# tottag.net
KiCad netlist of a schematic drawn in EAGLE
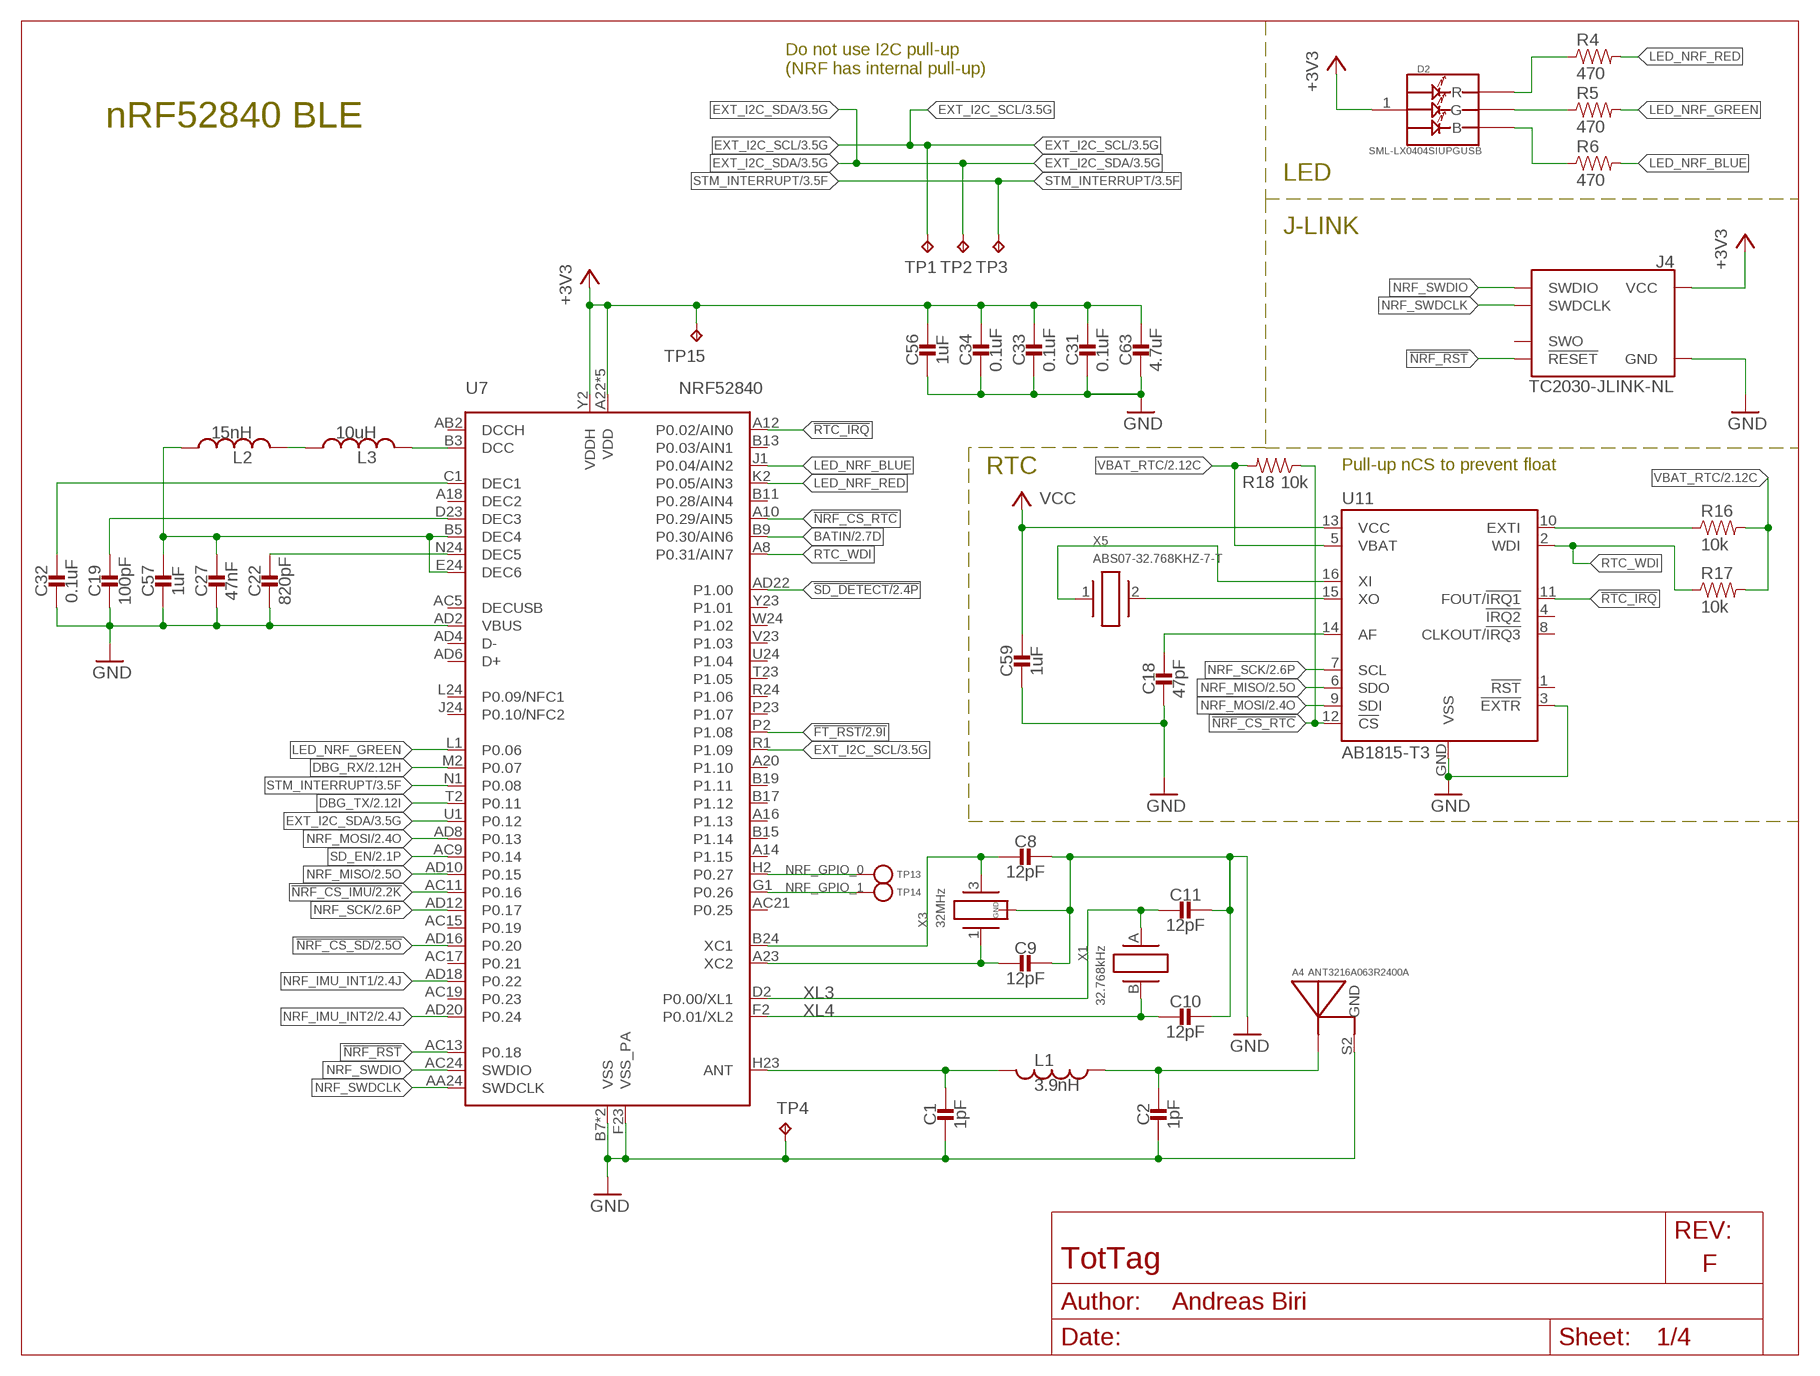
[diagram p0: schematic, sheet 1]
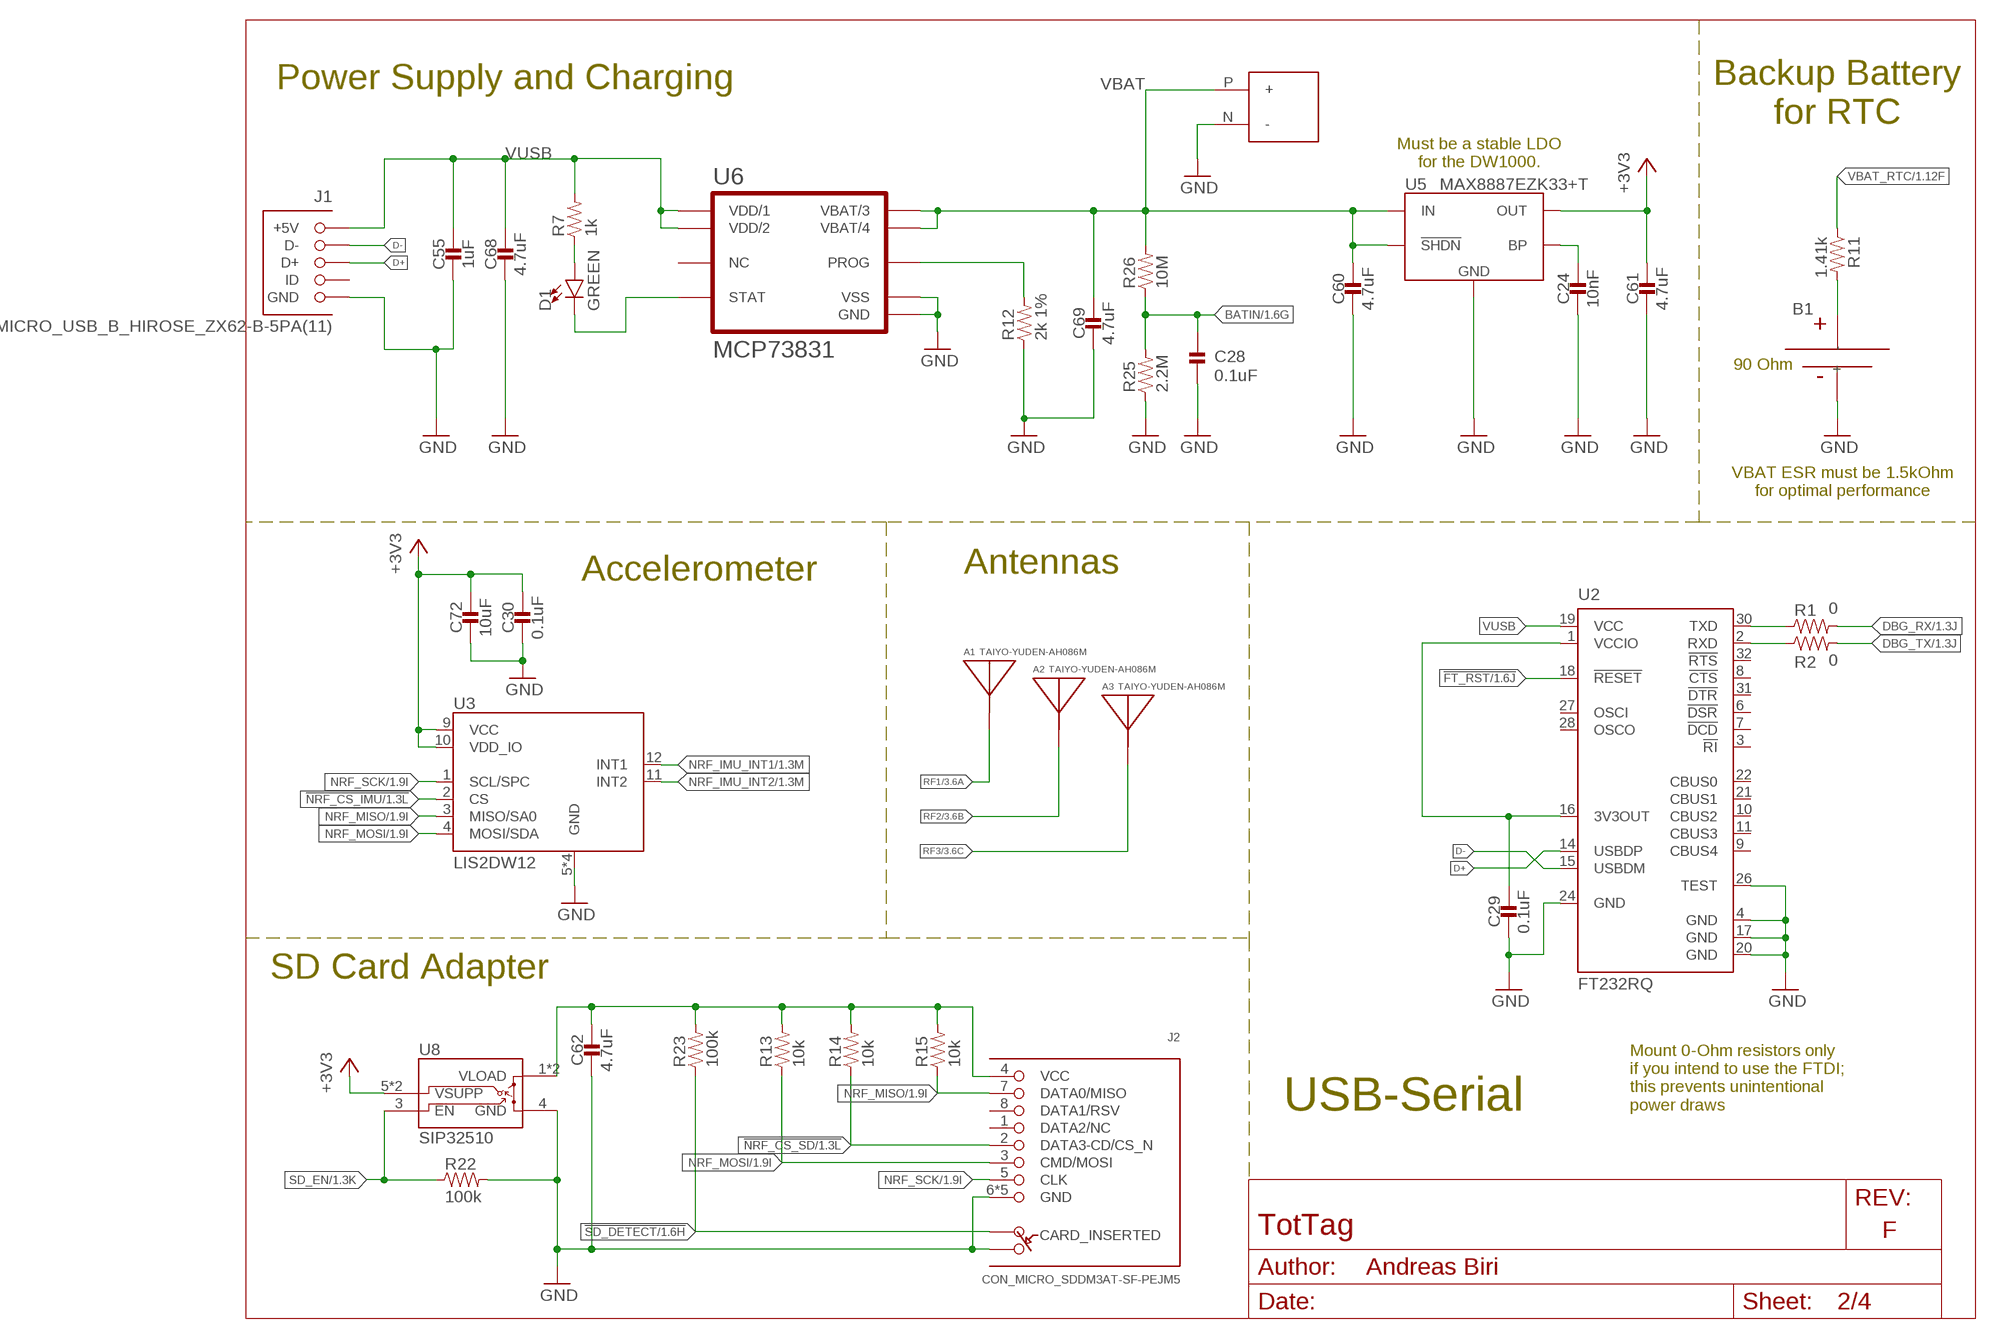
[diagram p1: schematic, sheet 2]
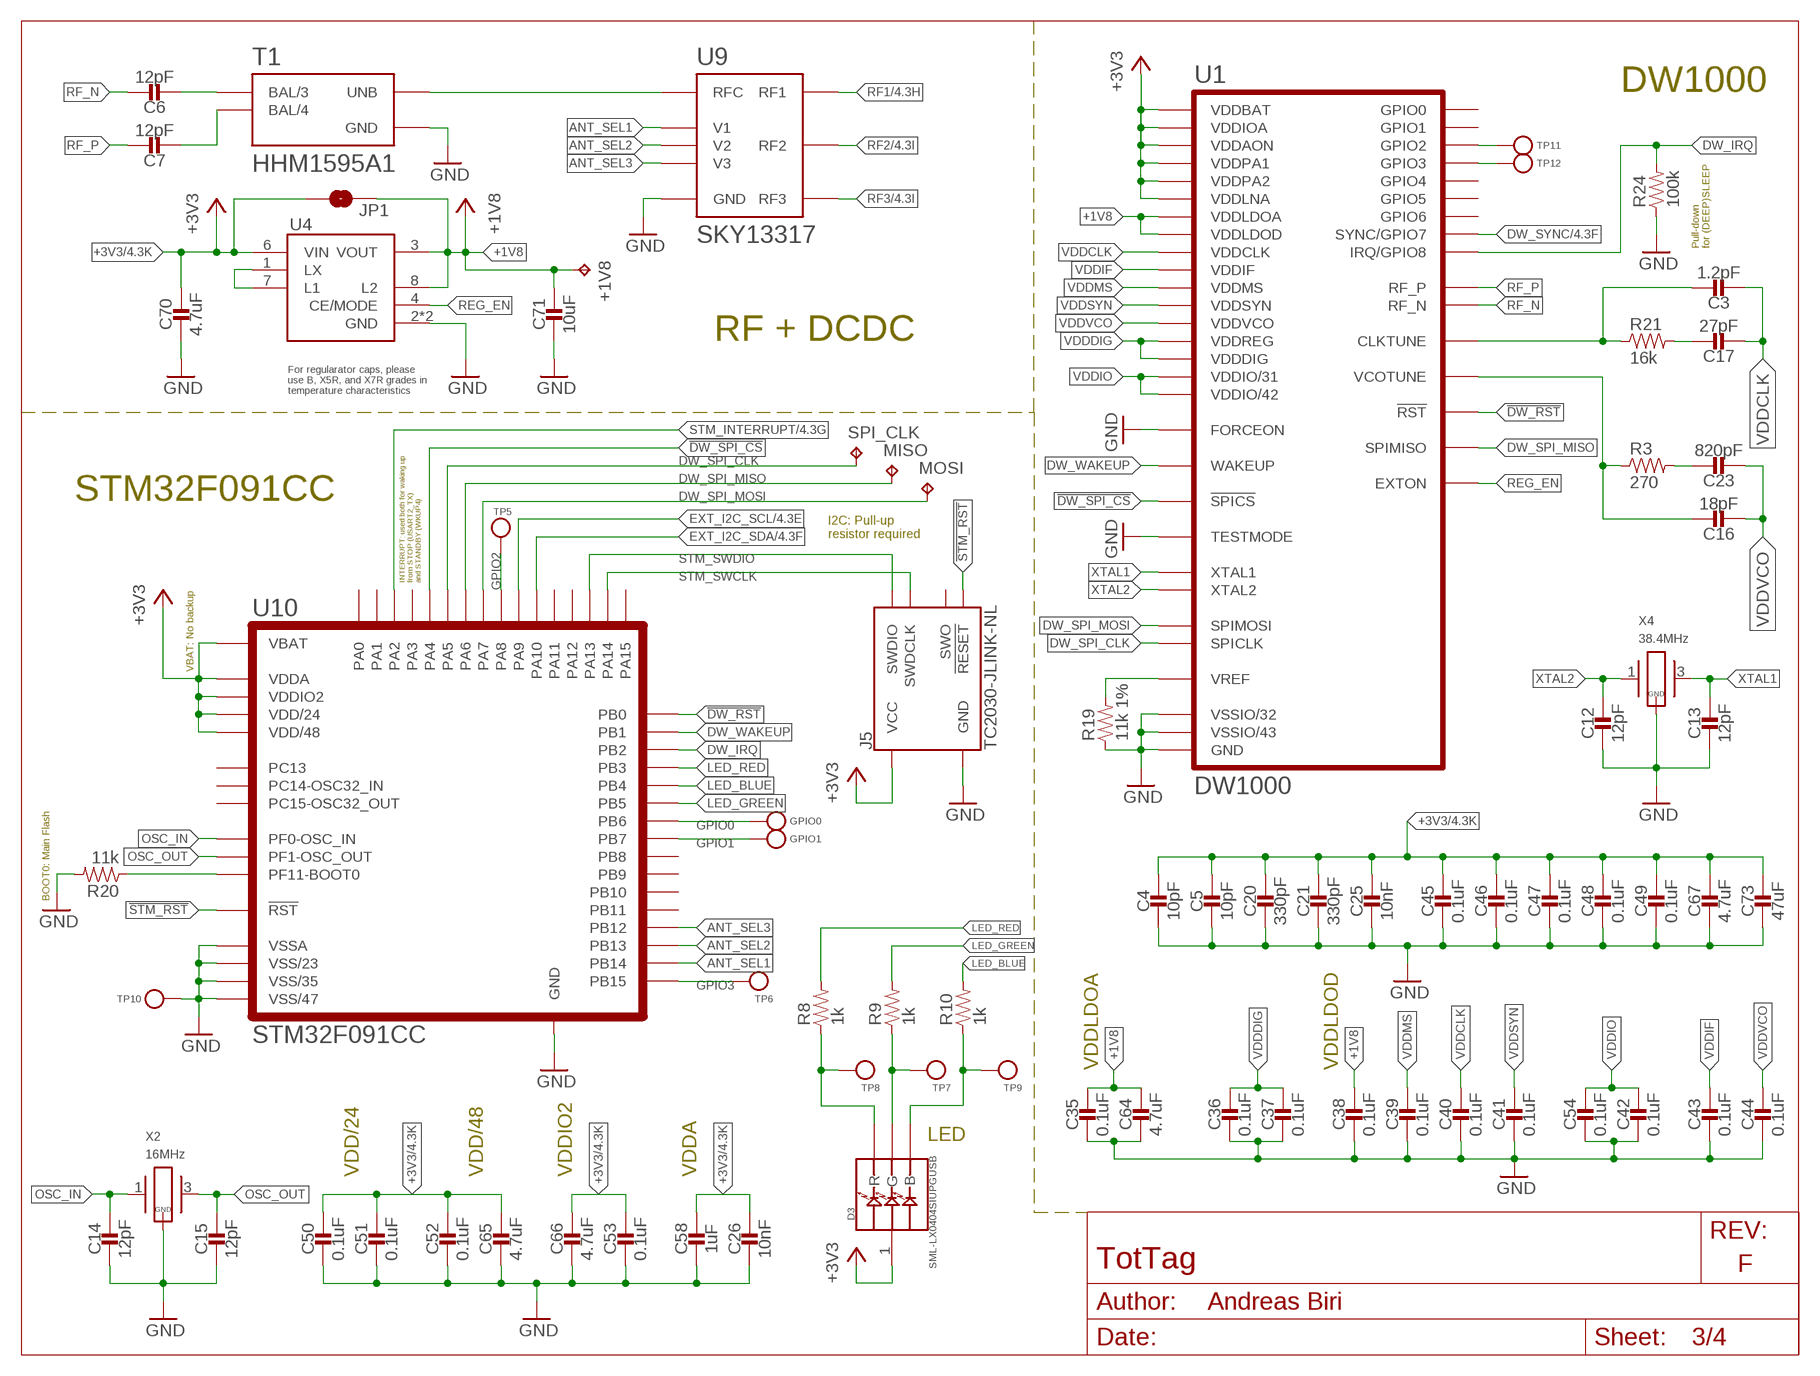
[diagram p2: schematic, sheet 3]
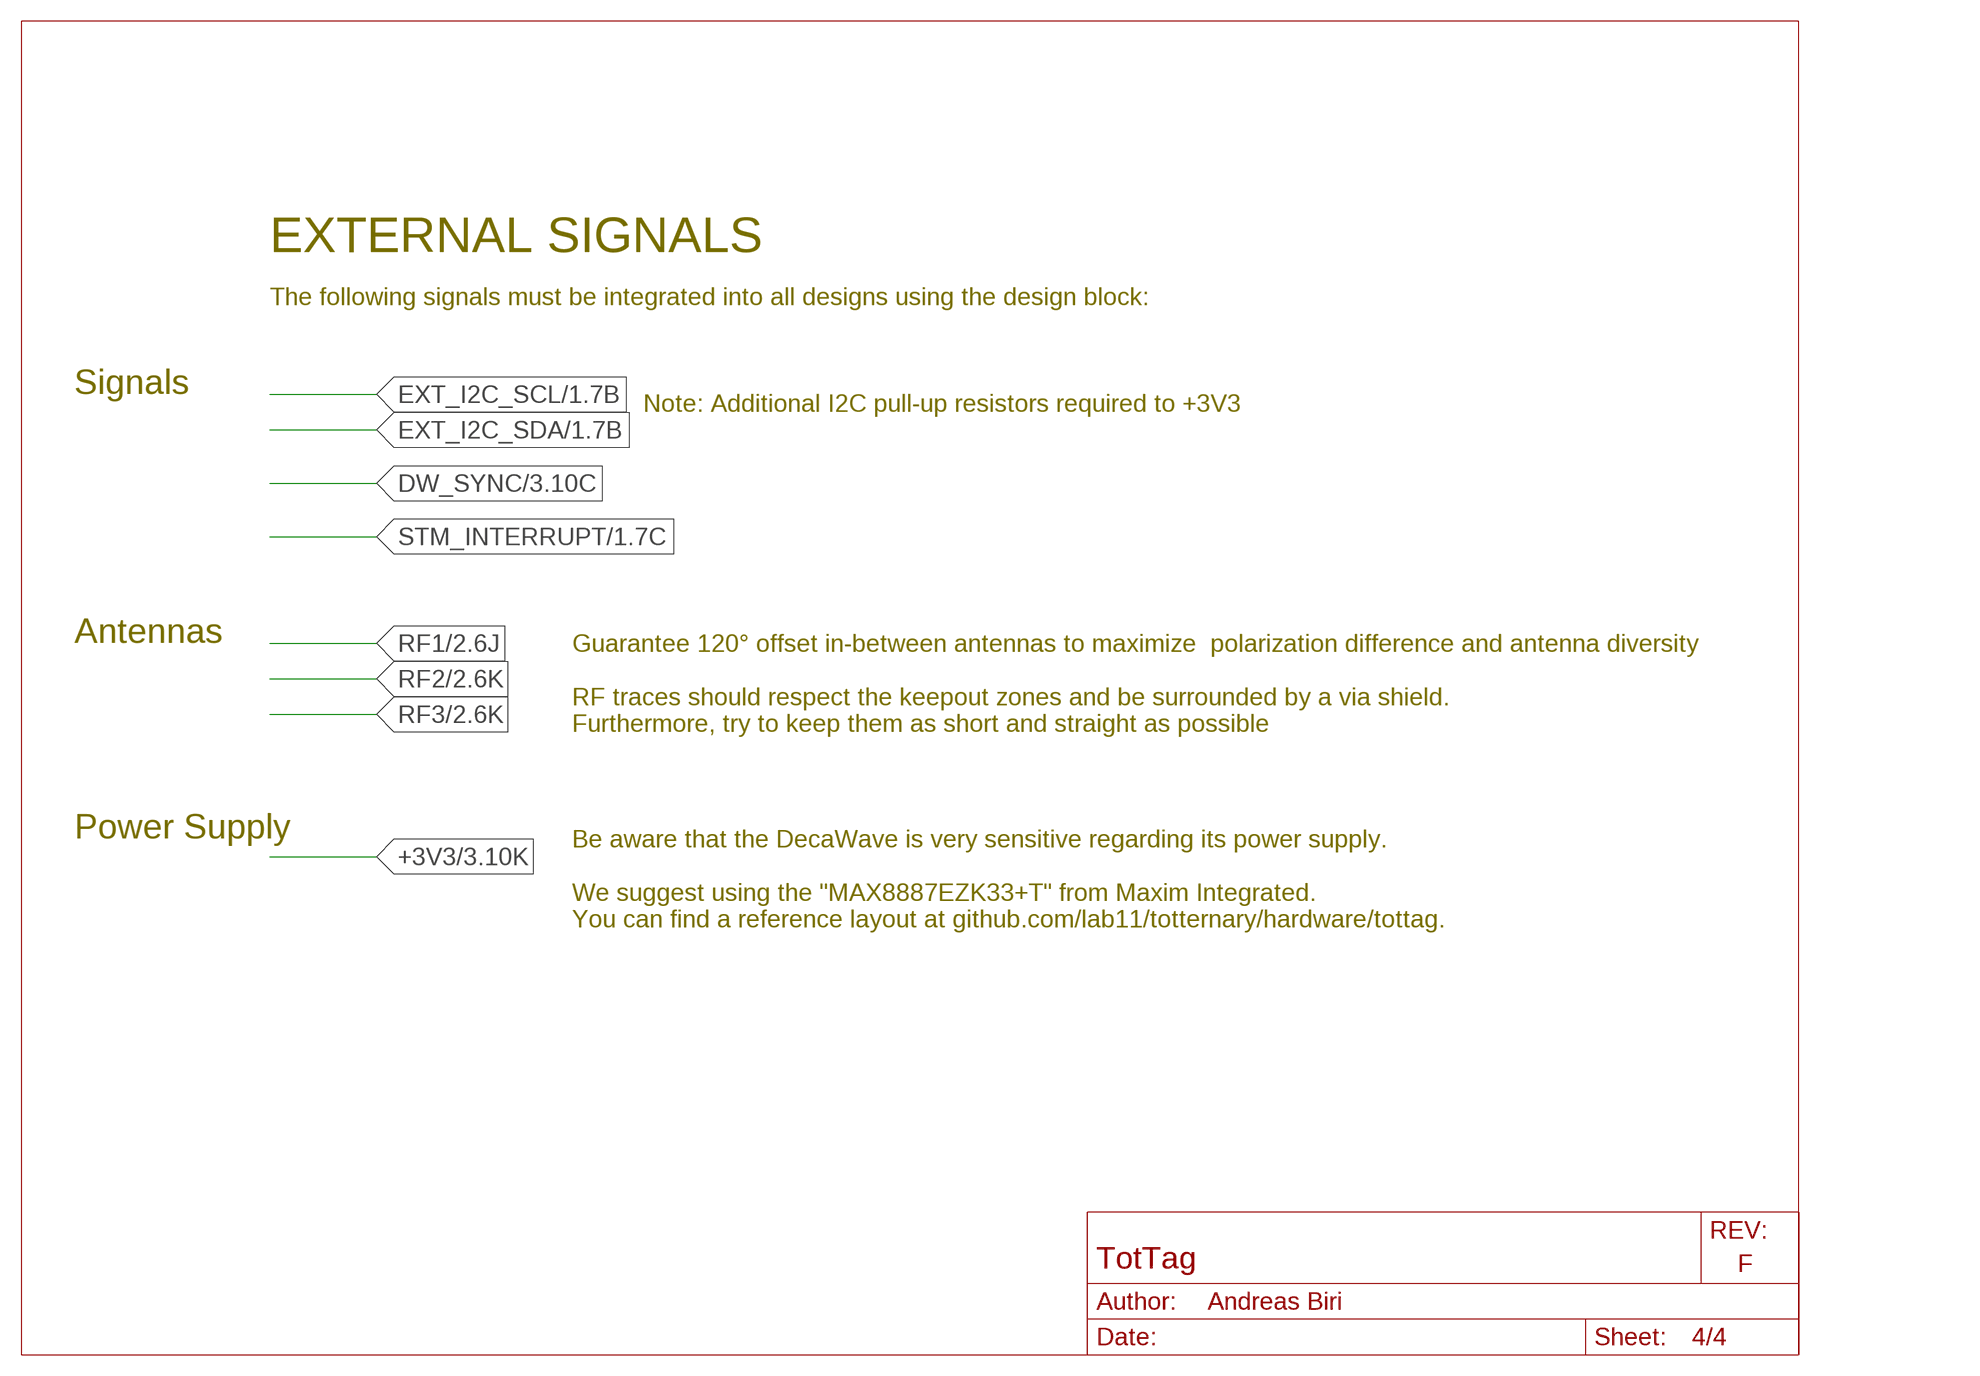
[diagram p3: schematic, sheet 4]

(export (version "E")
  (design (tool "Eeschema 10.0.6"))
  (components
    (comp (ref "+1V8")
      (value "TPTP06SQ")
      (footprint "eagle-import:TP06SQ")
      (libsource (lib "eagle-import") (part "TPTP06SQ"))
    )
    (comp (ref "C3")
      (value "1.2pF")
      (footprint "eagle-import:0402_CAP")
      (libsource (lib "eagle-import") (part "CAPACITOR0402_CAP"))
    )
    (comp (ref "C4")
      (value "10pF")
      (footprint "eagle-import:0402_CAP")
      (libsource (lib "eagle-import") (part "CAPACITOR0402_CAP"))
    )
    (comp (ref "C5")
      (value "10pF")
      (footprint "eagle-import:0402_CAP")
      (libsource (lib "eagle-import") (part "CAPACITOR0402_CAP"))
    )
    (comp (ref "C6")
      (value "12pF")
      (footprint "eagle-import:0201_CAP")
      (libsource (lib "eagle-import") (part "CAPACITOR0201_CAP"))
    )
    (comp (ref "C7")
      (value "12pF")
      (footprint "eagle-import:0201_CAP")
      (libsource (lib "eagle-import") (part "CAPACITOR0201_CAP"))
    )
    (comp (ref "C12")
      (value "12pF")
      (footprint "eagle-import:0402_CAP")
      (libsource (lib "eagle-import") (part "CAPACITOR0402_CAP"))
    )
    (comp (ref "C13")
      (value "12pF")
      (footprint "eagle-import:0402_CAP")
      (libsource (lib "eagle-import") (part "CAPACITOR0402_CAP"))
    )
    (comp (ref "C14")
      (value "12pF")
      (footprint "eagle-import:0402_CAP")
      (libsource (lib "eagle-import") (part "CAPACITOR0402_CAP"))
    )
    (comp (ref "C15")
      (value "12pF")
      (footprint "eagle-import:0402_CAP")
      (libsource (lib "eagle-import") (part "CAPACITOR0402_CAP"))
    )
    (comp (ref "C16")
      (value "18pF")
      (footprint "eagle-import:0402_CAP")
      (libsource (lib "eagle-import") (part "CAPACITOR0402_CAP"))
    )
    (comp (ref "C17")
      (value "27pF")
      (footprint "eagle-import:0402_CAP")
      (libsource (lib "eagle-import") (part "CAPACITOR0402_CAP"))
    )
    (comp (ref "C20")
      (value "330pF")
      (footprint "eagle-import:0402_CAP")
      (libsource (lib "eagle-import") (part "CAPACITOR0402_CAP"))
    )
    (comp (ref "C21")
      (value "330pF")
      (footprint "eagle-import:0402_CAP")
      (libsource (lib "eagle-import") (part "CAPACITOR0402_CAP"))
    )
    (comp (ref "C23")
      (value "820pF")
      (footprint "eagle-import:0402_CAP")
      (libsource (lib "eagle-import") (part "CAPACITOR0402_CAP"))
    )
    (comp (ref "C25")
      (value "10nF")
      (footprint "eagle-import:0402_CAP")
      (libsource (lib "eagle-import") (part "CAPACITOR0402_CAP"))
    )
    (comp (ref "C26")
      (value "10nF")
      (footprint "eagle-import:0402_CAP")
      (libsource (lib "eagle-import") (part "CAPACITOR0402_CAP"))
    )
    (comp (ref "C35")
      (value "0.1uF")
      (footprint "eagle-import:0402_CAP")
      (libsource (lib "eagle-import") (part "CAPACITOR0402_CAP"))
    )
    (comp (ref "C36")
      (value "0.1uF")
      (footprint "eagle-import:0402_CAP")
      (libsource (lib "eagle-import") (part "CAPACITOR0402_CAP"))
    )
    (comp (ref "C37")
      (value "0.1uF")
      (footprint "eagle-import:0402_CAP")
      (libsource (lib "eagle-import") (part "CAPACITOR0402_CAP"))
    )
    (comp (ref "C38")
      (value "0.1uF")
      (footprint "eagle-import:0402_CAP")
      (libsource (lib "eagle-import") (part "CAPACITOR0402_CAP"))
    )
    (comp (ref "C39")
      (value "0.1uF")
      (footprint "eagle-import:0402_CAP")
      (libsource (lib "eagle-import") (part "CAPACITOR0402_CAP"))
    )
    (comp (ref "C40")
      (value "0.1uF")
      (footprint "eagle-import:0402_CAP")
      (libsource (lib "eagle-import") (part "CAPACITOR0402_CAP"))
    )
    (comp (ref "C41")
      (value "0.1uF")
      (footprint "eagle-import:0402_CAP")
      (libsource (lib "eagle-import") (part "CAPACITOR0402_CAP"))
    )
    (comp (ref "C42")
      (value "0.1uF")
      (footprint "eagle-import:0402_CAP")
      (libsource (lib "eagle-import") (part "CAPACITOR0402_CAP"))
    )
    (comp (ref "C43")
      (value "0.1uF")
      (footprint "eagle-import:0402_CAP")
      (libsource (lib "eagle-import") (part "CAPACITOR0402_CAP"))
    )
    (comp (ref "C44")
      (value "0.1uF")
      (footprint "eagle-import:0402_CAP")
      (libsource (lib "eagle-import") (part "CAPACITOR0402_CAP"))
    )
    (comp (ref "C45")
      (value "0.1uF")
      (footprint "eagle-import:0402_CAP")
      (libsource (lib "eagle-import") (part "CAPACITOR0402_CAP"))
    )
    (comp (ref "C46")
      (value "0.1uF")
      (footprint "eagle-import:0402_CAP")
      (libsource (lib "eagle-import") (part "CAPACITOR0402_CAP"))
    )
    (comp (ref "C47")
      (value "0.1uF")
      (footprint "eagle-import:0402_CAP")
      (libsource (lib "eagle-import") (part "CAPACITOR0402_CAP"))
    )
    (comp (ref "C48")
      (value "0.1uF")
      (footprint "eagle-import:0402_CAP")
      (libsource (lib "eagle-import") (part "CAPACITOR0402_CAP"))
    )
    (comp (ref "C49")
      (value "0.1uF")
      (footprint "eagle-import:0402_CAP")
      (libsource (lib "eagle-import") (part "CAPACITOR0402_CAP"))
    )
    (comp (ref "C50")
      (value "0.1uF")
      (footprint "eagle-import:0402_CAP")
      (libsource (lib "eagle-import") (part "CAPACITOR0402_CAP"))
    )
    (comp (ref "C51")
      (value "0.1uF")
      (footprint "eagle-import:0402_CAP")
      (libsource (lib "eagle-import") (part "CAPACITOR0402_CAP"))
    )
    (comp (ref "C52")
      (value "0.1uF")
      (footprint "eagle-import:0402_CAP")
      (libsource (lib "eagle-import") (part "CAPACITOR0402_CAP"))
    )
    (comp (ref "C53")
      (value "0.1uF")
      (footprint "eagle-import:0402_CAP")
      (libsource (lib "eagle-import") (part "CAPACITOR0402_CAP"))
    )
    (comp (ref "C54")
      (value "0.1uF")
      (footprint "eagle-import:0402_CAP")
      (libsource (lib "eagle-import") (part "CAPACITOR0402_CAP"))
    )
    (comp (ref "C58")
      (value "1uF")
      (footprint "eagle-import:0402_CAP")
      (libsource (lib "eagle-import") (part "CAPACITOR0402_CAP"))
    )
    (comp (ref "C64")
      (value "4.7uF")
      (footprint "eagle-import:0402_CAP")
      (libsource (lib "eagle-import") (part "CAPACITOR0402_CAP"))
    )
    (comp (ref "C65")
      (value "4.7uF")
      (footprint "eagle-import:0402_CAP")
      (libsource (lib "eagle-import") (part "CAPACITOR0402_CAP"))
    )
    (comp (ref "C66")
      (value "4.7uF")
      (footprint "eagle-import:0402_CAP")
      (libsource (lib "eagle-import") (part "CAPACITOR0402_CAP"))
    )
    (comp (ref "C67")
      (value "4.7uF")
      (footprint "eagle-import:0402_CAP")
      (libsource (lib "eagle-import") (part "CAPACITOR0402_CAP"))
    )
    (comp (ref "C70")
      (value "4.7uF")
      (footprint "eagle-import:0402_CAP")
      (libsource (lib "eagle-import") (part "CAPACITOR0402_CAP"))
    )
    (comp (ref "C71")
      (value "10uF")
      (footprint "eagle-import:0402_CAP")
      (libsource (lib "eagle-import") (part "CAPACITOR0402_CAP"))
    )
    (comp (ref "C73")
      (value "47uF")
      (footprint "eagle-import:0603_CAP")
      (libsource (lib "eagle-import") (part "CAPACITOR0603_CAP"))
    )
    (comp (ref "D3")
      (value "SML-LX0404SIUPGUSB")
      (footprint "eagle-import:1MM_SQ_4PAD")
      (fields (field (name "MANUFACTURER") "Lumex Opto"))
      (libsource (lib "eagle-import") (part "SML-LX0404SIUPGUSB"))
    )
    (comp (ref "GPIO0")
      (value "TEST-POINT")
      (footprint "eagle-import:PAD.03X.03")
      (libsource (lib "eagle-import") (part "TEST-POINT"))
    )
    (comp (ref "GPIO1")
      (value "TEST-POINT")
      (footprint "eagle-import:PAD.03X.03")
      (libsource (lib "eagle-import") (part "TEST-POINT"))
    )
    (comp (ref "J5")
      (value "TC2030-JLINK-NL")
      (footprint "eagle-import:TC2030-IDC-NL")
      (libsource (lib "eagle-import") (part "TC2030-JLINK-NL"))
    )
    (comp (ref "JP1")
      (value "JUMPER-SMT_2_NO_NO-SILK")
      (footprint "eagle-import:SMT-JUMPER_2_NO_NO-SILK")
      (libsource (lib "eagle-import") (part "JUMPER-SMT_2_NO_NO-SILK"))
    )
    (comp (ref "MISO")
      (value "TPTP06SQ")
      (footprint "eagle-import:TP06SQ")
      (libsource (lib "eagle-import") (part "TPTP06SQ"))
    )
    (comp (ref "MOSI")
      (value "TPTP06SQ")
      (footprint "eagle-import:TP06SQ")
      (libsource (lib "eagle-import") (part "TPTP06SQ"))
    )
    (comp (ref "R3")
      (value "270")
      (footprint "eagle-import:0402_RES")
      (libsource (lib "eagle-import") (part "RESISTOR0402_RES"))
    )
    (comp (ref "R8")
      (value "1k")
      (footprint "eagle-import:0402_RES")
      (libsource (lib "eagle-import") (part "RESISTOR0402_RES"))
    )
    (comp (ref "R9")
      (value "1k")
      (footprint "eagle-import:0402_RES")
      (libsource (lib "eagle-import") (part "RESISTOR0402_RES"))
    )
    (comp (ref "R10")
      (value "1k")
      (footprint "eagle-import:0402_RES")
      (libsource (lib "eagle-import") (part "RESISTOR0402_RES"))
    )
    (comp (ref "R19")
      (value "11k 1%")
      (footprint "eagle-import:0402_RES")
      (libsource (lib "eagle-import") (part "RESISTOR0402_RES"))
    )
    (comp (ref "R20")
      (value "11k")
      (footprint "eagle-import:0402_RES")
      (libsource (lib "eagle-import") (part "RESISTOR0402_RES"))
    )
    (comp (ref "R21")
      (value "16k")
      (footprint "eagle-import:0402_RES")
      (libsource (lib "eagle-import") (part "RESISTOR0402_RES"))
    )
    (comp (ref "R24")
      (value "100k")
      (footprint "eagle-import:0402_RES")
      (libsource (lib "eagle-import") (part "RESISTOR0402_RES"))
    )
    (comp (ref "SPI_CLK")
      (value "TPTP06SQ")
      (footprint "eagle-import:TP06SQ")
      (libsource (lib "eagle-import") (part "TPTP06SQ"))
    )
    (comp (ref "T1")
      (value "HHM1595A1")
      (footprint "eagle-import:EIA-0805")
      (fields (field (name "MANUFACTURER") "TDK Corporation"))
      (libsource (lib "eagle-import") (part "HHM1595A1"))
    )
    (comp (ref "TP5")
      (value "TEST-POINT")
      (footprint "eagle-import:PAD.03X.03")
      (libsource (lib "eagle-import") (part "TEST-POINT"))
    )
    (comp (ref "TP6")
      (value "TEST-POINT")
      (footprint "eagle-import:PAD.03X.03")
      (libsource (lib "eagle-import") (part "TEST-POINT"))
    )
    (comp (ref "TP7")
      (value "TEST-POINT")
      (footprint "eagle-import:PAD.03X.03")
      (libsource (lib "eagle-import") (part "TEST-POINT"))
    )
    (comp (ref "TP8")
      (value "TEST-POINT")
      (footprint "eagle-import:PAD.03X.03")
      (libsource (lib "eagle-import") (part "TEST-POINT"))
    )
    (comp (ref "TP9")
      (value "TEST-POINT")
      (footprint "eagle-import:PAD.03X.03")
      (libsource (lib "eagle-import") (part "TEST-POINT"))
    )
    (comp (ref "TP10")
      (value "TEST-POINT")
      (footprint "eagle-import:PAD.03X.03")
      (libsource (lib "eagle-import") (part "TEST-POINT"))
    )
    (comp (ref "TP11")
      (value "TEST-POINT")
      (footprint "eagle-import:PAD.03X.03")
      (libsource (lib "eagle-import") (part "TEST-POINT"))
    )
    (comp (ref "TP12")
      (value "TEST-POINT")
      (footprint "eagle-import:PAD.03X.03")
      (libsource (lib "eagle-import") (part "TEST-POINT"))
    )
    (comp (ref "U1")
      (value "DW1000")
      (footprint "eagle-import:QFN-48-DW1000")
      (fields (field (name "MANUFACTURER") "Decawave Limited") (field (name "MPN") "DW1000-I-TR13"))
      (libsource (lib "eagle-import") (part "DW1000"))
    )
    (comp (ref "U4")
      (value "XCL206B")
      (footprint "eagle-import:XCL20X")
      (fields (field (name "MPN") "XCL206B183CR-G"))
      (libsource (lib "eagle-import") (part "XCL206B"))
    )
    (comp (ref "U9")
      (value "SKY13317")
      (footprint "eagle-import:MLPQ-UT-8")
      (fields (field (name "MANUFACTURER") "Skyworks Solutions Inc.") (field (name "MPN") "SKY13317-373LF"))
      (libsource (lib "eagle-import") (part "SKY13317"))
    )
    (comp (ref "U10")
      (value "STM32F091CC")
      (footprint "eagle-import:UFQFPN-48")
      (fields (field (name "MANUFACTURER") "STMicroelectronics") (field (name "MPN") "STM32F091CCU6"))
      (libsource (lib "eagle-import") (part "STM32F091CC"))
    )
    (comp (ref "X2")
      (value "16MHz")
      (footprint "eagle-import:FA-20H")
      (description "16MHz ±10ppm Crystal 8pF 80 Ohms 4-SMD, No Lead")
      (fields (field (name "MANUFACTURER") "EPSON"))
      (libsource (lib "eagle-import") (part "FA-20H"))
    )
    (comp (ref "X4")
      (value "38.4MHz")
      (footprint "eagle-import:FA-20H")
      (description "38.4MHz ±10ppm Crystal 8.5pF 40 Ohms 4-SMD, No Lead")
      (fields (field (name "MANUFACTURER") "EPSON"))
      (libsource (lib "eagle-import") (part "FA-20H"))
    )
    (comp (ref "A1")
      (value "TAIYO-YUDEN-AH086M")
      (footprint "eagle-import:TAIYO-YUDEN-AH086M")
      (libsource (lib "eagle-import") (part "TAIYO-YUDEN-AH086M"))
    )
    (comp (ref "A2")
      (value "TAIYO-YUDEN-AH086M")
      (footprint "eagle-import:TAIYO-YUDEN-AH086M")
      (libsource (lib "eagle-import") (part "TAIYO-YUDEN-AH086M"))
    )
    (comp (ref "A3")
      (value "TAIYO-YUDEN-AH086M")
      (footprint "eagle-import:TAIYO-YUDEN-AH086M")
      (libsource (lib "eagle-import") (part "TAIYO-YUDEN-AH086M"))
    )
    (comp (ref "B1")
      (value "MS518SE")
      (footprint "eagle-import:MS518SE-FL35E")
      (fields (field (name "MANUFACTURER") "Seiko") (field (name "MPN") "MS518SE-FL35E"))
      (libsource (lib "eagle-import") (part "MS518SE"))
    )
    (comp (ref "C24")
      (value "10nF")
      (footprint "eagle-import:0402_CAP")
      (libsource (lib "eagle-import") (part "CAPACITOR0402_CAP"))
    )
    (comp (ref "C28")
      (value "0.1uF")
      (footprint "eagle-import:0402_CAP")
      (libsource (lib "eagle-import") (part "CAPACITOR0402_CAP"))
    )
    (comp (ref "C29")
      (value "0.1uF")
      (footprint "eagle-import:0402_CAP")
      (fields (field (name "MPN") "GRM155R71C104KA88J "))
      (libsource (lib "eagle-import") (part "CAPACITOR0402_CAP"))
    )
    (comp (ref "C30")
      (value "0.1uF")
      (footprint "eagle-import:0402_CAP")
      (fields (field (name "MPN") "GRM155R71C104KA88J "))
      (libsource (lib "eagle-import") (part "CAPACITOR0402_CAP"))
    )
    (comp (ref "C55")
      (value "1uF")
      (footprint "eagle-import:0402_CAP")
      (libsource (lib "eagle-import") (part "CAPACITOR0402_CAP"))
    )
    (comp (ref "C60")
      (value "4.7uF")
      (footprint "eagle-import:0402_CAP")
      (libsource (lib "eagle-import") (part "CAPACITOR0402_CAP"))
    )
    (comp (ref "C61")
      (value "4.7uF")
      (footprint "eagle-import:0402_CAP")
      (libsource (lib "eagle-import") (part "CAPACITOR0402_CAP"))
    )
    (comp (ref "C62")
      (value "4.7uF")
      (footprint "eagle-import:0402_CAP")
      (description "CAP CER 4.7UF 6.3V X5R 0402")
      (fields (field (name "MANUFACTURER") "TDK") (field (name "MPN") "C1005X5R0J475K050BC"))
      (libsource (lib "eagle-import") (part "CAPACITOR0402_CAP"))
    )
    (comp (ref "C68")
      (value "4.7uF")
      (footprint "eagle-import:0402_CAP")
      (libsource (lib "eagle-import") (part "CAPACITOR0402_CAP"))
    )
    (comp (ref "C69")
      (value "4.7uF")
      (footprint "eagle-import:0402_CAP")
      (libsource (lib "eagle-import") (part "CAPACITOR0402_CAP"))
    )
    (comp (ref "C72")
      (value "10uF")
      (footprint "eagle-import:0603_CAP")
      (fields (field (name "MPN") "GRM188R60J106ME47D "))
      (libsource (lib "eagle-import") (part "CAPACITOR0603_CAP"))
    )
    (comp (ref "D1")
      (value "GREEN")
      (footprint "eagle-import:LED-0603")
      (libsource (lib "eagle-import") (part "LED0603"))
    )
    (comp (ref "J1")
      (value "MICRO_USB_B_HIROSE_ZX62-B-5PA(11)")
      (footprint "eagle-import:USB_MICRO_B-HIROSE-ZX62-B-5PA(11)")
      (libsource (lib "eagle-import") (part "MICRO_USB_B_HIROSE_ZX62-B-5PA(11)"))
    )
    (comp (ref "J2")
      (value "CON_MICRO_SDDM3AT-SF-PEJM5")
      (footprint "eagle-import:DM3AT-SF-PEJM5")
      (libsource (lib "eagle-import") (part "CON_MICRO_SDDM3AT-SF-PEJM5"))
    )
    (comp (ref "J3")
      (value "BAT_HOLE")
      (footprint "eagle-import:BATTERY_HOLE")
      (libsource (lib "eagle-import") (part "BAT_HOLE"))
    )
    (comp (ref "R1")
      (value "0")
      (footprint "eagle-import:0402_RES")
      (libsource (lib "eagle-import") (part "RESISTOR0402_RES"))
    )
    (comp (ref "R2")
      (value "0")
      (footprint "eagle-import:0402_RES")
      (libsource (lib "eagle-import") (part "RESISTOR0402_RES"))
    )
    (comp (ref "R7")
      (value "1k")
      (footprint "eagle-import:0402_RES")
      (libsource (lib "eagle-import") (part "RESISTOR0402_RES"))
    )
    (comp (ref "R11")
      (value "1.41k")
      (footprint "eagle-import:0402_RES")
      (fields (field (name "MPN") "RC0402JR-0710KL"))
      (libsource (lib "eagle-import") (part "RESISTOR0402_RES"))
    )
    (comp (ref "R12")
      (value "2k 1%")
      (footprint "eagle-import:0402_RES")
      (libsource (lib "eagle-import") (part "RESISTOR0402_RES"))
    )
    (comp (ref "R13")
      (value "10k")
      (footprint "eagle-import:0402_RES")
      (libsource (lib "eagle-import") (part "RESISTOR0402_RES"))
    )
    (comp (ref "R14")
      (value "10k")
      (footprint "eagle-import:0402_RES")
      (libsource (lib "eagle-import") (part "RESISTOR0402_RES"))
    )
    (comp (ref "R15")
      (value "10k")
      (footprint "eagle-import:0402_RES")
      (libsource (lib "eagle-import") (part "RESISTOR0402_RES"))
    )
    (comp (ref "R22")
      (value "100k")
      (footprint "eagle-import:0402_RES")
      (libsource (lib "eagle-import") (part "RESISTOR0402_RES"))
    )
    (comp (ref "R23")
      (value "100k")
      (footprint "eagle-import:0402_RES")
      (libsource (lib "eagle-import") (part "RESISTOR0402_RES"))
    )
    (comp (ref "R25")
      (value "2.2M")
      (footprint "eagle-import:0402_RES")
      (libsource (lib "eagle-import") (part "RESISTOR0402_RES"))
    )
    (comp (ref "R26")
      (value "10M")
      (footprint "eagle-import:0402_RES")
      (libsource (lib "eagle-import") (part "RESISTOR0402_RES"))
    )
    (comp (ref "U2")
      (value "FT232RQ")
      (footprint "eagle-import:QFN32")
      (libsource (lib "eagle-import") (part "FT232RQ"))
    )
    (comp (ref "U3")
      (value "LIS2DW12")
      (footprint "eagle-import:LGA-12")
      (fields (field (name "MANUFACTURER") "STMicroelectronics") (field (name "MPN") "LIS2DW12TR"))
      (libsource (lib "eagle-import") (part "LIS2DW12"))
    )
    (comp (ref "U5")
      (value "MAX8887EZK33+T")
      (footprint "eagle-import:SOT-23-5")
      (libsource (lib "eagle-import") (part "MAX8887EZK33+T"))
    )
    (comp (ref "U6")
      (value "MCP73831")
      (footprint "eagle-import:DFN-8-MCP")
      (fields (field (name "MANUFACTURER") "Microchip Technology") (field (name "MPN") "MCP73831T-2ACI/MC"))
      (libsource (lib "eagle-import") (part "MCP73831"))
    )
    (comp (ref "U8")
      (value "SIP32510")
      (footprint "eagle-import:TSOT23-6")
      (fields (field (name "MANUFACTURER") "Vishay") (field (name "MPN") "SIP32510DT-T1-GE3"))
      (libsource (lib "eagle-import") (part "SIP32510"))
    )
    (comp (ref "A4")
      (value "ANT3216A063R2400A")
      (footprint "eagle-import:ANT3216A063R2400A")
      (fields (field (name "MANUFACTURER") "YAGEO"))
      (libsource (lib "eagle-import") (part "ANT3216A063R2400A"))
    )
    (comp (ref "C1")
      (value "1pF")
      (footprint "eagle-import:0402_CAP")
      (fields (field (name "MPN") "GJM1555C1H1R0CB01D "))
      (libsource (lib "eagle-import") (part "CAPACITOR0402_CAP"))
    )
    (comp (ref "C2")
      (value "1pF")
      (footprint "eagle-import:0402_CAP")
      (fields (field (name "MPN") "GJM1555C1H1R0CB01D"))
      (libsource (lib "eagle-import") (part "CAPACITOR0402_CAP"))
    )
    (comp (ref "C8")
      (value "12pF")
      (footprint "eagle-import:0402_CAP")
      (fields (field (name "MPN") "GRM1555C1H120GA01D "))
      (libsource (lib "eagle-import") (part "CAPACITOR0402_CAP"))
    )
    (comp (ref "C9")
      (value "12pF")
      (footprint "eagle-import:0402_CAP")
      (fields (field (name "MPN") "GRM1555C1H120GA01D "))
      (libsource (lib "eagle-import") (part "CAPACITOR0402_CAP"))
    )
    (comp (ref "C10")
      (value "12pF")
      (footprint "eagle-import:0402_CAP")
      (fields (field (name "MPN") "GRM1555C1H120GA01D "))
      (libsource (lib "eagle-import") (part "CAPACITOR0402_CAP"))
    )
    (comp (ref "C11")
      (value "12pF")
      (footprint "eagle-import:0402_CAP")
      (fields (field (name "MPN") "GRM1555C1H120GA01D "))
      (libsource (lib "eagle-import") (part "CAPACITOR0402_CAP"))
    )
    (comp (ref "C18")
      (value "47pF")
      (footprint "eagle-import:0402_CAP")
      (fields (field (name "MPN") "GRM1555C1H470JA01D "))
      (libsource (lib "eagle-import") (part "CAPACITOR0402_CAP"))
    )
    (comp (ref "C19")
      (value "100pF")
      (footprint "eagle-import:0402_CAP")
      (fields (field (name "MPN") "GRM1555C1H101JA01D "))
      (libsource (lib "eagle-import") (part "CAPACITOR0402_CAP"))
    )
    (comp (ref "C22")
      (value "820pF")
      (footprint "eagle-import:0402_CAP")
      (fields (field (name "MPN") "CL05C821JB5NFNC"))
      (libsource (lib "eagle-import") (part "CAPACITOR0402_CAP"))
    )
    (comp (ref "C27")
      (value "47nF")
      (footprint "eagle-import:0402_CAP")
      (fields (field (name "MPN") "C1005X7R1C473K050BC "))
      (libsource (lib "eagle-import") (part "CAPACITOR0402_CAP"))
    )
    (comp (ref "C31")
      (value "0.1uF")
      (footprint "eagle-import:0402_CAP")
      (fields (field (name "MPN") "GRM155R71C104KA88J "))
      (libsource (lib "eagle-import") (part "CAPACITOR0402_CAP"))
    )
    (comp (ref "C32")
      (value "0.1uF")
      (footprint "eagle-import:0402_CAP")
      (fields (field (name "MPN") "GRM155R71C104KA88J "))
      (libsource (lib "eagle-import") (part "CAPACITOR0402_CAP"))
    )
    (comp (ref "C33")
      (value "0.1uF")
      (footprint "eagle-import:0402_CAP")
      (fields (field (name "MPN") "GRM155R71C104KA88J "))
      (libsource (lib "eagle-import") (part "CAPACITOR0402_CAP"))
    )
    (comp (ref "C34")
      (value "0.1uF")
      (footprint "eagle-import:0402_CAP")
      (libsource (lib "eagle-import") (part "CAPACITOR0402_CAP"))
    )
    (comp (ref "C56")
      (value "1uF")
      (footprint "eagle-import:0402_CAP")
      (libsource (lib "eagle-import") (part "CAPACITOR0402_CAP"))
    )
    (comp (ref "C57")
      (value "1uF")
      (footprint "eagle-import:0402_CAP")
      (fields (field (name "MPN") "GRM155R70G105KA12D "))
      (libsource (lib "eagle-import") (part "CAPACITOR0402_CAP"))
    )
    (comp (ref "C59")
      (value "1uF")
      (footprint "eagle-import:0402_CAP")
      (fields (field (name "MPN") "GRM155R70G105KA12D "))
      (libsource (lib "eagle-import") (part "CAPACITOR0402_CAP"))
    )
    (comp (ref "C63")
      (value "4.7uF")
      (footprint "eagle-import:0402_CAP")
      (libsource (lib "eagle-import") (part "CAPACITOR0402_CAP"))
    )
    (comp (ref "D2")
      (value "SML-LX0404SIUPGUSB")
      (footprint "eagle-import:1MM_SQ_4PAD")
      (fields (field (name "MANUFACTURER") "Lumex Opto"))
      (libsource (lib "eagle-import") (part "SML-LX0404SIUPGUSB"))
    )
    (comp (ref "J4")
      (value "TC2030-JLINK-NL")
      (footprint "eagle-import:TC2030-IDC-NL")
      (libsource (lib "eagle-import") (part "TC2030-JLINK-NL"))
    )
    (comp (ref "L1")
      (value "3.9nH")
      (footprint "eagle-import:0402_CAP")
      (fields (field (name "MPN") "AISC-0402-3N9G-T "))
      (libsource (lib "eagle-import") (part "INDUCTOR0402"))
    )
    (comp (ref "L2")
      (value "15nH")
      (footprint "eagle-import:0402_CAP")
      (fields (field (name "MPN") "HK100515NJ-T "))
      (libsource (lib "eagle-import") (part "INDUCTOR0402"))
    )
    (comp (ref "L3")
      (value "10uH")
      (footprint "eagle-import:0603_CAP")
      (fields (field (name "MPN") "LQM18FN100M00D "))
      (libsource (lib "eagle-import") (part "INDUCTOR0603"))
    )
    (comp (ref "R4")
      (value "470")
      (footprint "eagle-import:0402_RES")
      (libsource (lib "eagle-import") (part "RESISTOR0402_RES"))
    )
    (comp (ref "R5")
      (value "470")
      (footprint "eagle-import:0402_RES")
      (libsource (lib "eagle-import") (part "RESISTOR0402_RES"))
    )
    (comp (ref "R6")
      (value "470")
      (footprint "eagle-import:0402_RES")
      (libsource (lib "eagle-import") (part "RESISTOR0402_RES"))
    )
    (comp (ref "R16")
      (value "10k")
      (footprint "eagle-import:0402_RES")
      (fields (field (name "MPN") "RC0402JR-0710KL"))
      (libsource (lib "eagle-import") (part "RESISTOR0402_RES"))
    )
    (comp (ref "R17")
      (value "10k")
      (footprint "eagle-import:0402_RES")
      (fields (field (name "MPN") "RC0402JR-0710KL"))
      (libsource (lib "eagle-import") (part "RESISTOR0402_RES"))
    )
    (comp (ref "R18")
      (value "10k")
      (footprint "eagle-import:0402_RES")
      (fields (field (name "MPN") "RC0402JR-0710KL"))
      (libsource (lib "eagle-import") (part "RESISTOR0402_RES"))
    )
    (comp (ref "TP1")
      (value "TPTP06SQ")
      (footprint "eagle-import:TP06SQ")
      (libsource (lib "eagle-import") (part "TPTP06SQ"))
    )
    (comp (ref "TP2")
      (value "TPTP06SQ")
      (footprint "eagle-import:TP06SQ")
      (libsource (lib "eagle-import") (part "TPTP06SQ"))
    )
    (comp (ref "TP3")
      (value "TPTP06SQ")
      (footprint "eagle-import:TP06SQ")
      (libsource (lib "eagle-import") (part "TPTP06SQ"))
    )
    (comp (ref "TP4")
      (value "TPTP06SQ")
      (footprint "eagle-import:TP06SQ")
      (libsource (lib "eagle-import") (part "TPTP06SQ"))
    )
    (comp (ref "TP13")
      (value "TEST-POINT")
      (footprint "eagle-import:PAD.03X.03")
      (libsource (lib "eagle-import") (part "TEST-POINT"))
    )
    (comp (ref "TP14")
      (value "TEST-POINT")
      (footprint "eagle-import:PAD.03X.03")
      (libsource (lib "eagle-import") (part "TEST-POINT"))
    )
    (comp (ref "TP15")
      (value "TPTP06SQ")
      (footprint "eagle-import:TP06SQ")
      (libsource (lib "eagle-import") (part "TPTP06SQ"))
    )
    (comp (ref "U7")
      (value "NRF52840")
      (footprint "eagle-import:AQFN73")
      (fields (field (name "MANUFACTURER") "NORIDIC SEMICONDUCTOR"))
      (libsource (lib "eagle-import") (part "NRF52840"))
    )
    (comp (ref "U11")
      (value "AB1815-T3")
      (footprint "eagle-import:QFN-16-3MM")
      (fields (field (name "MANUFACTURER") "Abracon"))
      (libsource (lib "eagle-import") (part "AB1815-T3"))
    )
    (comp (ref "X1")
      (value "32.768kHz")
      (footprint "eagle-import:ABS05")
      (fields (field (name "MANUFACTURER") "Abracon") (field (name "MPN") "ABS05-32.768KHZ-9-T"))
      (libsource (lib "eagle-import") (part "ABS05-32.768KHZ-9-T"))
    )
    (comp (ref "X3")
      (value "32MHz")
      (footprint "eagle-import:TXC-7V")
      (fields (field (name "MANUFACTURER") "TXC CORPORATION") (field (name "MPN") "7M-32.000MAHV-T"))
      (libsource (lib "eagle-import") (part "7V-32.000MAHV-T"))
    )
    (comp (ref "X5")
      (value "ABS07-32.768KHZ-7-T")
      (footprint "eagle-import:2-SMD")
      (fields (field (name "MANUFACTURER") "ABRACON") (field (name "MPN") "ABS07-32.768KHZ-7-T "))
      (libsource (lib "eagle-import") (part "ABS07-32.768KHZ-7-T"))
    )
  )
  (nets
    (net (code "1") (name "+1V8") (class "Default")
      (node (ref "+1V8") (pin "TP") (pinfunction "TP_TP") (pintype "input"))
      (node (ref "C35") (pin "1") (pinfunction "1_1") (pintype "bidirectional"))
      (node (ref "C38") (pin "1") (pinfunction "1_1") (pintype "bidirectional"))
      (node (ref "C64") (pin "1") (pinfunction "1_1") (pintype "bidirectional"))
      (node (ref "C71") (pin "1") (pinfunction "1_1") (pintype "bidirectional"))
      (node (ref "JP1") (pin "2") (pinfunction "2_2") (pintype "passive"))
      (node (ref "U1") (pin "26") (pinfunction "VDDLDOD_26") (pintype "power_in"))
      (node (ref "U1") (pin "48") (pinfunction "VDDLDOA_48") (pintype "power_in"))
      (node (ref "U4") (pin "3") (pinfunction "VOUT_3") (pintype "bidirectional"))
      (node (ref "U4") (pin "8") (pinfunction "L2_8") (pintype "bidirectional"))
    )
    (net (code "2") (name "+3V3") (class "Default")
      (node (ref "C20") (pin "1") (pinfunction "1_1") (pintype "bidirectional"))
      (node (ref "C21") (pin "1") (pinfunction "1_1") (pintype "bidirectional"))
      (node (ref "C25") (pin "1") (pinfunction "1_1") (pintype "bidirectional"))
      (node (ref "C26") (pin "1") (pinfunction "1_1") (pintype "bidirectional"))
      (node (ref "C30") (pin "1") (pinfunction "1_1") (pintype "bidirectional"))
      (node (ref "C31") (pin "1") (pinfunction "1_1") (pintype "bidirectional"))
      (node (ref "C33") (pin "1") (pinfunction "1_1") (pintype "bidirectional"))
      (node (ref "C34") (pin "1") (pinfunction "1_1") (pintype "bidirectional"))
      (node (ref "C4") (pin "1") (pinfunction "1_1") (pintype "bidirectional"))
      (node (ref "C45") (pin "1") (pinfunction "1_1") (pintype "bidirectional"))
      (node (ref "C46") (pin "1") (pinfunction "1_1") (pintype "bidirectional"))
      (node (ref "C47") (pin "1") (pinfunction "1_1") (pintype "bidirectional"))
      (node (ref "C48") (pin "1") (pinfunction "1_1") (pintype "bidirectional"))
      (node (ref "C49") (pin "1") (pinfunction "1_1") (pintype "bidirectional"))
      (node (ref "C5") (pin "1") (pinfunction "1_1") (pintype "bidirectional"))
      (node (ref "C50") (pin "1") (pinfunction "1_1") (pintype "bidirectional"))
      (node (ref "C51") (pin "1") (pinfunction "1_1") (pintype "bidirectional"))
      (node (ref "C52") (pin "1") (pinfunction "1_1") (pintype "bidirectional"))
      (node (ref "C53") (pin "1") (pinfunction "1_1") (pintype "bidirectional"))
      (node (ref "C56") (pin "1") (pinfunction "1_1") (pintype "bidirectional"))
      (node (ref "C58") (pin "1") (pinfunction "1_1") (pintype "bidirectional"))
      (node (ref "C61") (pin "1") (pinfunction "1_1") (pintype "bidirectional"))
      (node (ref "C63") (pin "1") (pinfunction "1_1") (pintype "bidirectional"))
      (node (ref "C65") (pin "1") (pinfunction "1_1") (pintype "bidirectional"))
      (node (ref "C66") (pin "1") (pinfunction "1_1") (pintype "bidirectional"))
      (node (ref "C67") (pin "1") (pinfunction "1_1") (pintype "bidirectional"))
      (node (ref "C70") (pin "1") (pinfunction "1_1") (pintype "bidirectional"))
      (node (ref "C72") (pin "1") (pinfunction "1_1") (pintype "bidirectional"))
      (node (ref "C73") (pin "1") (pinfunction "1_1") (pintype "bidirectional"))
      (node (ref "D2") (pin "1") (pinfunction "VDD_1") (pintype "bidirectional"))
      (node (ref "D3") (pin "1") (pinfunction "VDD_1") (pintype "bidirectional"))
      (node (ref "J4") (pin "1") (pinfunction "VCC_1") (pintype "bidirectional"))
      (node (ref "J5") (pin "1") (pinfunction "VCC_1") (pintype "bidirectional"))
      (node (ref "JP1") (pin "1") (pinfunction "1_1") (pintype "passive"))
      (node (ref "TP15") (pin "TP") (pinfunction "TP_TP") (pintype "input"))
      (node (ref "U1") (pin "15") (pinfunction "VDDLNA_15") (pintype "power_in"))
      (node (ref "U1") (pin "18") (pinfunction "VDDPA1_18") (pintype "power_in"))
      (node (ref "U1") (pin "19") (pinfunction "VDDPA2_19") (pintype "power_in"))
      (node (ref "U1") (pin "25") (pinfunction "VDDAON_25") (pintype "power_in"))
      (node (ref "U1") (pin "28") (pinfunction "VDDIOA_28") (pintype "power_in"))
      (node (ref "U1") (pin "47") (pinfunction "VDDBAT_47") (pintype "power_in"))
      (node (ref "U10") (pin "1") (pinfunction "VBAT_1") (pintype "power_in"))
      (node (ref "U10") (pin "24") (pinfunction "VDD/24_24") (pintype "power_in"))
      (node (ref "U10") (pin "36") (pinfunction "VDDIO2_36") (pintype "power_in"))
      (node (ref "U10") (pin "48") (pinfunction "VDD/48_48") (pintype "power_in"))
      (node (ref "U10") (pin "9") (pinfunction "VDDA_9") (pintype "power_in"))
      (node (ref "U3") (pin "10") (pinfunction "VDD_IO_10") (pintype "bidirectional"))
      (node (ref "U3") (pin "9") (pinfunction "VCC_9") (pintype "bidirectional"))
      (node (ref "U4") (pin "6") (pinfunction "VIN_6") (pintype "bidirectional"))
      (node (ref "U5") (pin "5") (pinfunction "OUT_5") (pintype "bidirectional"))
      (node (ref "U7") (pin "A22") (pinfunction "VDD_A22") (pintype "bidirectional"))
      (node (ref "U7") (pin "AD14") (pinfunction "VDD_AD14") (pintype "bidirectional"))
      (node (ref "U7") (pin "AD23") (pinfunction "VDD_AD23") (pintype "bidirectional"))
      (node (ref "U7") (pin "B1") (pinfunction "VDD_B1") (pintype "bidirectional"))
      (node (ref "U7") (pin "W1") (pinfunction "VDD_W1") (pintype "bidirectional"))
      (node (ref "U7") (pin "Y2") (pinfunction "VDDH_Y2") (pintype "bidirectional"))
      (node (ref "U8") (pin "5") (pinfunction "VSUPP_5") (pintype "bidirectional"))
      (node (ref "U8") (pin "6") (pinfunction "VSUPP_6") (pintype "bidirectional"))
    )
    (net (code "3") (name "ANT_SEL1") (class "Default")
      (node (ref "U10") (pin "27") (pinfunction "PB14_27") (pintype "bidirectional"))
      (node (ref "U9") (pin "3") (pinfunction "V1_3") (pintype "bidirectional"))
    )
    (net (code "4") (name "ANT_SEL2") (class "Default")
      (node (ref "U10") (pin "26") (pinfunction "PB13_26") (pintype "bidirectional"))
      (node (ref "U9") (pin "6") (pinfunction "V2_6") (pintype "bidirectional"))
    )
    (net (code "5") (name "ANT_SEL3") (class "Default")
      (node (ref "U10") (pin "25") (pinfunction "PB12_25") (pintype "bidirectional"))
      (node (ref "U9") (pin "7") (pinfunction "V3_7") (pintype "bidirectional"))
    )
    (net (code "6") (name "BATIN") (class "Default")
      (node (ref "C28") (pin "2") (pinfunction "2_2") (pintype "bidirectional"))
      (node (ref "R25") (pin "2") (pinfunction "2_2") (pintype "passive"))
      (node (ref "R26") (pin "1") (pinfunction "1_1") (pintype "passive"))
      (node (ref "U7") (pin "B9") (pinfunction "P0.30/AIN6_B9") (pintype "bidirectional"))
    )
    (net (code "7") (name "D+") (class "Default")
      (node (ref "J1") (pin "3") (pinfunction "D+_3") (pintype "bidirectional"))
      (node (ref "U2") (pin "14") (pinfunction "USBDP_14") (pintype "bidirectional"))
    )
    (net (code "8") (name "D-") (class "Default")
      (node (ref "J1") (pin "2") (pinfunction "D-_2") (pintype "bidirectional"))
      (node (ref "U2") (pin "15") (pinfunction "USBDM_15") (pintype "bidirectional"))
    )
    (net (code "9") (name "DBG_RX") (class "Default")
      (node (ref "R1") (pin "2") (pinfunction "2_2") (pintype "passive"))
      (node (ref "U7") (pin "M2") (pinfunction "P0.07_M2") (pintype "bidirectional"))
    )
    (net (code "10") (name "DBG_TX") (class "Default")
      (node (ref "R2") (pin "2") (pinfunction "2_2") (pintype "passive"))
      (node (ref "U7") (pin "T2") (pinfunction "P0.11_T2") (pintype "bidirectional"))
    )
    (net (code "11") (name "DW_IRQ") (class "Default")
      (node (ref "R24") (pin "2") (pinfunction "2_2") (pintype "passive"))
      (node (ref "U1") (pin "45") (pinfunction "IRQ/GPIO8_45") (pintype "bidirectional"))
      (node (ref "U10") (pin "20") (pinfunction "PB2_20") (pintype "bidirectional"))
    )
    (net (code "12") (name "DW_SPI_CLK") (class "Default")
      (node (ref "SPI_CLK") (pin "TP") (pinfunction "TP_TP") (pintype "input"))
      (node (ref "U1") (pin "41") (pinfunction "SPICLK_41") (pintype "input"))
      (node (ref "U10") (pin "15") (pinfunction "PA5_15") (pintype "bidirectional"))
    )
    (net (code "13") (name "DW_SPI_MISO") (class "Default")
      (node (ref "MISO") (pin "TP") (pinfunction "TP_TP") (pintype "input"))
      (node (ref "U1") (pin "40") (pinfunction "SPIMISO_40") (pintype "output"))
      (node (ref "U10") (pin "16") (pinfunction "PA6_16") (pintype "bidirectional"))
    )
    (net (code "14") (name "DW_SPI_MOSI") (class "Default")
      (node (ref "MOSI") (pin "TP") (pinfunction "TP_TP") (pintype "input"))
      (node (ref "U1") (pin "39") (pinfunction "SPIMOSI_39") (pintype "input"))
      (node (ref "U10") (pin "17") (pinfunction "PA7_17") (pintype "bidirectional"))
    )
    (net (code "15") (name "DW_SYNC") (class "Default")
      (node (ref "U1") (pin "29") (pinfunction "SYNC/GPIO7_29") (pintype "bidirectional"))
    )
    (net (code "16") (name "DW_WAKEUP") (class "Default")
      (node (ref "U1") (pin "23") (pinfunction "WAKEUP_23") (pintype "input"))
      (node (ref "U10") (pin "19") (pinfunction "PB1_19") (pintype "bidirectional"))
    )
    (net (code "17") (name "EXT_I2C_SCL") (class "Default")
      (node (ref "TP1") (pin "TP") (pinfunction "TP_TP") (pintype "input"))
      (node (ref "U10") (pin "30") (pinfunction "PA9_30") (pintype "bidirectional"))
      (node (ref "U7") (pin "R1") (pinfunction "P1.09_R1") (pintype "bidirectional"))
    )
    (net (code "18") (name "EXT_I2C_SDA") (class "Default")
      (node (ref "TP2") (pin "TP") (pinfunction "TP_TP") (pintype "input"))
      (node (ref "U10") (pin "31") (pinfunction "PA10_31") (pintype "bidirectional"))
      (node (ref "U7") (pin "U1") (pinfunction "P0.12_U1") (pintype "bidirectional"))
    )
    (net (code "19") (name "GND") (class "Default")
      (node (ref "A4") (pin "S2") (pinfunction "GND_S2") (pintype "bidirectional"))
      (node (ref "B1") (pin "-") (pinfunction "-_-") (pintype "bidirectional"))
      (node (ref "C1") (pin "2") (pinfunction "2_2") (pintype "bidirectional"))
      (node (ref "C10") (pin "1") (pinfunction "1_1") (pintype "bidirectional"))
      (node (ref "C11") (pin "1") (pinfunction "1_1") (pintype "bidirectional"))
      (node (ref "C12") (pin "2") (pinfunction "2_2") (pintype "bidirectional"))
      (node (ref "C13") (pin "2") (pinfunction "2_2") (pintype "bidirectional"))
      (node (ref "C14") (pin "2") (pinfunction "2_2") (pintype "bidirectional"))
      (node (ref "C15") (pin "2") (pinfunction "2_2") (pintype "bidirectional"))
      (node (ref "C18") (pin "2") (pinfunction "2_2") (pintype "bidirectional"))
      (node (ref "C19") (pin "2") (pinfunction "2_2") (pintype "bidirectional"))
      (node (ref "C2") (pin "2") (pinfunction "2_2") (pintype "bidirectional"))
      (node (ref "C20") (pin "2") (pinfunction "2_2") (pintype "bidirectional"))
      (node (ref "C21") (pin "2") (pinfunction "2_2") (pintype "bidirectional"))
      (node (ref "C22") (pin "2") (pinfunction "2_2") (pintype "bidirectional"))
      (node (ref "C24") (pin "2") (pinfunction "2_2") (pintype "bidirectional"))
      (node (ref "C25") (pin "2") (pinfunction "2_2") (pintype "bidirectional"))
      (node (ref "C26") (pin "2") (pinfunction "2_2") (pintype "bidirectional"))
      (node (ref "C27") (pin "2") (pinfunction "2_2") (pintype "bidirectional"))
      (node (ref "C28") (pin "1") (pinfunction "1_1") (pintype "bidirectional"))
      (node (ref "C29") (pin "2") (pinfunction "2_2") (pintype "bidirectional"))
      (node (ref "C30") (pin "2") (pinfunction "2_2") (pintype "bidirectional"))
      (node (ref "C31") (pin "2") (pinfunction "2_2") (pintype "bidirectional"))
      (node (ref "C32") (pin "2") (pinfunction "2_2") (pintype "bidirectional"))
      (node (ref "C33") (pin "2") (pinfunction "2_2") (pintype "bidirectional"))
      (node (ref "C34") (pin "2") (pinfunction "2_2") (pintype "bidirectional"))
      (node (ref "C35") (pin "2") (pinfunction "2_2") (pintype "bidirectional"))
      (node (ref "C36") (pin "2") (pinfunction "2_2") (pintype "bidirectional"))
      (node (ref "C37") (pin "2") (pinfunction "2_2") (pintype "bidirectional"))
      (node (ref "C38") (pin "2") (pinfunction "2_2") (pintype "bidirectional"))
      (node (ref "C39") (pin "2") (pinfunction "2_2") (pintype "bidirectional"))
      (node (ref "C4") (pin "2") (pinfunction "2_2") (pintype "bidirectional"))
      (node (ref "C40") (pin "2") (pinfunction "2_2") (pintype "bidirectional"))
      (node (ref "C41") (pin "2") (pinfunction "2_2") (pintype "bidirectional"))
      (node (ref "C42") (pin "2") (pinfunction "2_2") (pintype "bidirectional"))
      (node (ref "C43") (pin "2") (pinfunction "2_2") (pintype "bidirectional"))
      (node (ref "C44") (pin "2") (pinfunction "2_2") (pintype "bidirectional"))
      (node (ref "C45") (pin "2") (pinfunction "2_2") (pintype "bidirectional"))
      (node (ref "C46") (pin "2") (pinfunction "2_2") (pintype "bidirectional"))
      (node (ref "C47") (pin "2") (pinfunction "2_2") (pintype "bidirectional"))
      (node (ref "C48") (pin "2") (pinfunction "2_2") (pintype "bidirectional"))
      (node (ref "C49") (pin "2") (pinfunction "2_2") (pintype "bidirectional"))
      (node (ref "C5") (pin "2") (pinfunction "2_2") (pintype "bidirectional"))
      (node (ref "C50") (pin "2") (pinfunction "2_2") (pintype "bidirectional"))
      (node (ref "C51") (pin "2") (pinfunction "2_2") (pintype "bidirectional"))
      (node (ref "C52") (pin "2") (pinfunction "2_2") (pintype "bidirectional"))
      (node (ref "C53") (pin "2") (pinfunction "2_2") (pintype "bidirectional"))
      (node (ref "C54") (pin "2") (pinfunction "2_2") (pintype "bidirectional"))
      (node (ref "C55") (pin "2") (pinfunction "2_2") (pintype "bidirectional"))
      (node (ref "C56") (pin "2") (pinfunction "2_2") (pintype "bidirectional"))
      (node (ref "C57") (pin "2") (pinfunction "2_2") (pintype "bidirectional"))
      (node (ref "C58") (pin "2") (pinfunction "2_2") (pintype "bidirectional"))
      (node (ref "C59") (pin "2") (pinfunction "2_2") (pintype "bidirectional"))
      (node (ref "C60") (pin "2") (pinfunction "2_2") (pintype "bidirectional"))
      (node (ref "C61") (pin "2") (pinfunction "2_2") (pintype "bidirectional"))
      (node (ref "C62") (pin "2") (pinfunction "2_2") (pintype "bidirectional"))
      (node (ref "C63") (pin "2") (pinfunction "2_2") (pintype "bidirectional"))
      (node (ref "C64") (pin "2") (pinfunction "2_2") (pintype "bidirectional"))
      (node (ref "C65") (pin "2") (pinfunction "2_2") (pintype "bidirectional"))
      (node (ref "C66") (pin "2") (pinfunction "2_2") (pintype "bidirectional"))
      (node (ref "C67") (pin "2") (pinfunction "2_2") (pintype "bidirectional"))
      (node (ref "C68") (pin "2") (pinfunction "2_2") (pintype "bidirectional"))
      (node (ref "C69") (pin "2") (pinfunction "2_2") (pintype "bidirectional"))
      (node (ref "C70") (pin "2") (pinfunction "2_2") (pintype "bidirectional"))
      (node (ref "C71") (pin "2") (pinfunction "2_2") (pintype "bidirectional"))
      (node (ref "C72") (pin "2") (pinfunction "2_2") (pintype "bidirectional"))
      (node (ref "C73") (pin "2") (pinfunction "2_2") (pintype "bidirectional"))
      (node (ref "C8") (pin "1") (pinfunction "1_1") (pintype "bidirectional"))
      (node (ref "C9") (pin "1") (pinfunction "1_1") (pintype "bidirectional"))
      (node (ref "J1") (pin "5") (pinfunction "GND_5") (pintype "bidirectional"))
      (node (ref "J2") (pin "6") (pinfunction "GND_6") (pintype "bidirectional"))
      (node (ref "J2") (pin "B") (pinfunction "B_B") (pintype "bidirectional"))
      (node (ref "J2") (pin "MOUNT0") (pinfunction "GND_MOUNT0") (pintype "bidirectional"))
      (node (ref "J2") (pin "MOUNT1") (pinfunction "GND_MOUNT1") (pintype "bidirectional"))
      (node (ref "J2") (pin "MOUNT2") (pinfunction "GND_MOUNT2") (pintype "bidirectional"))
      (node (ref "J2") (pin "MOUNT3") (pinfunction "GND_MOUNT3") (pintype "bidirectional"))
      (node (ref "J3") (pin "N") (pinfunction "-_N") (pintype "bidirectional"))
      (node (ref "J4") (pin "5") (pinfunction "GND_5") (pintype "bidirectional"))
      (node (ref "J5") (pin "5") (pinfunction "GND_5") (pintype "bidirectional"))
      (node (ref "R12") (pin "1") (pinfunction "1_1") (pintype "passive"))
      (node (ref "R19") (pin "1") (pinfunction "1_1") (pintype "passive"))
      (node (ref "R20") (pin "2") (pinfunction "2_2") (pintype "passive"))
      (node (ref "R22") (pin "2") (pinfunction "2_2") (pintype "passive"))
      (node (ref "R24") (pin "1") (pinfunction "1_1") (pintype "passive"))
      (node (ref "R25") (pin "1") (pinfunction "1_1") (pintype "passive"))
      (node (ref "T1") (pin "2") (pinfunction "GND_2") (pintype "power_in"))
      (node (ref "T1") (pin "5") (pinfunction "GND_5") (pintype "power_in"))
      (node (ref "TP10") (pin "P$1") (pinfunction "TESTPOINT_P$1") (pintype "bidirectional"))
      (node (ref "TP4") (pin "TP") (pinfunction "TP_TP") (pintype "input"))
      (node (ref "U1") (pin "22") (pinfunction "FORCEON_22") (pintype "input"))
      (node (ref "U1") (pin "32") (pinfunction "VSSIO/32_32") (pintype "bidirectional"))
      (node (ref "U1") (pin "43") (pinfunction "VSSIO/43_43") (pintype "bidirectional"))
      (node (ref "U1") (pin "46") (pinfunction "TESTMODE_46") (pintype "input"))
      (node (ref "U1") (pin "GND") (pinfunction "GND_GND") (pintype "power_in"))
      (node (ref "U10") (pin "23") (pinfunction "VSS/23_23") (pintype "power_in"))
      (node (ref "U10") (pin "35") (pinfunction "VSS/35_35") (pintype "power_in"))
      (node (ref "U10") (pin "47") (pinfunction "VSS/47_47") (pintype "power_in"))
      (node (ref "U10") (pin "8") (pinfunction "VSSA_8") (pintype "power_in"))
      (node (ref "U10") (pin "GND") (pinfunction "GND_GND") (pintype "power_in"))
      (node (ref "U11") (pin "3") (pinfunction "~{EXTR}_3") (pintype "bidirectional"))
      (node (ref "U11") (pin "GND") (pinfunction "VSS_GND") (pintype "bidirectional"))
      (node (ref "U2") (pin "17") (pinfunction "GND_17") (pintype "power_in"))
      (node (ref "U2") (pin "20") (pinfunction "GND_20") (pintype "power_in"))
      (node (ref "U2") (pin "24") (pinfunction "GND_24") (pintype "power_in"))
      (node (ref "U2") (pin "26") (pinfunction "TEST_26") (pintype "input"))
      (node (ref "U2") (pin "4") (pinfunction "GND_4") (pintype "power_in"))
      (node (ref "U3") (pin "5") (pinfunction "GND_5") (pintype "bidirectional"))
      (node (ref "U3") (pin "6") (pinfunction "GND_6") (pintype "bidirectional"))
      (node (ref "U3") (pin "7") (pinfunction "GND_7") (pintype "bidirectional"))
      (node (ref "U3") (pin "8") (pinfunction "GND_8") (pintype "bidirectional"))
      (node (ref "U4") (pin "2") (pinfunction "GND_2") (pintype "bidirectional"))
      (node (ref "U4") (pin "5") (pinfunction "GND_5") (pintype "bidirectional"))
      (node (ref "U5") (pin "2") (pinfunction "GND_2") (pintype "bidirectional"))
      (node (ref "U6") (pin "6") (pinfunction "VSS_6") (pintype "power_in"))
      (node (ref "U6") (pin "GND") (pinfunction "GND_GND") (pintype "power_in"))
      (node (ref "U7") (pin "AD2") (pinfunction "VBUS_AD2") (pintype "bidirectional"))
      (node (ref "U7") (pin "B7") (pinfunction "VSS_B7") (pintype "bidirectional"))
      (node (ref "U7") (pin "F23") (pinfunction "VSS_PA_F23") (pintype "bidirectional"))
      (node (ref "U7") (pin "GND") (pinfunction "VSS_GND") (pintype "bidirectional"))
      (node (ref "U8") (pin "4") (pinfunction "GND_4") (pintype "bidirectional"))
      (node (ref "U9") (pin "GND") (pinfunction "GND_GND") (pintype "power_in"))
      (node (ref "X2") (pin "2") (pinfunction "GND_2") (pintype "bidirectional"))
      (node (ref "X2") (pin "4") (pinfunction "GND_4") (pintype "bidirectional"))
      (node (ref "X3") (pin "2") (pinfunction "GND_2") (pintype "bidirectional"))
      (node (ref "X3") (pin "4") (pinfunction "GND_4") (pintype "bidirectional"))
      (node (ref "X4") (pin "2") (pinfunction "GND_2") (pintype "bidirectional"))
      (node (ref "X4") (pin "4") (pinfunction "GND_4") (pintype "bidirectional"))
    )
    (net (code "20") (name "GPIO0") (class "Default")
      (node (ref "GPIO0") (pin "P$1") (pinfunction "TESTPOINT_P$1") (pintype "bidirectional"))
      (node (ref "U10") (pin "42") (pinfunction "PB6_42") (pintype "bidirectional"))
    )
    (net (code "21") (name "GPIO1") (class "Default")
      (node (ref "GPIO1") (pin "P$1") (pinfunction "TESTPOINT_P$1") (pintype "bidirectional"))
      (node (ref "U10") (pin "43") (pinfunction "PB7_43") (pintype "bidirectional"))
    )
    (net (code "22") (name "GPIO2") (class "Default")
      (node (ref "TP5") (pin "P$1") (pinfunction "TESTPOINT_P$1") (pintype "bidirectional"))
      (node (ref "U10") (pin "29") (pinfunction "PA8_29") (pintype "bidirectional"))
    )
    (net (code "23") (name "GPIO3") (class "Default")
      (node (ref "TP6") (pin "P$1") (pinfunction "TESTPOINT_P$1") (pintype "bidirectional"))
      (node (ref "U10") (pin "28") (pinfunction "PB15_28") (pintype "bidirectional"))
    )
    (net (code "24") (name "LED_BLUE") (class "Default")
      (node (ref "R10") (pin "2") (pinfunction "2_2") (pintype "passive"))
      (node (ref "U10") (pin "40") (pinfunction "PB4_40") (pintype "bidirectional"))
    )
    (net (code "25") (name "LED_GREEN") (class "Default")
      (node (ref "R9") (pin "2") (pinfunction "2_2") (pintype "passive"))
      (node (ref "U10") (pin "41") (pinfunction "PB5_41") (pintype "bidirectional"))
    )
    (net (code "26") (name "LED_NRF_BLUE") (class "Default")
      (node (ref "R6") (pin "2") (pinfunction "2_2") (pintype "passive"))
      (node (ref "U7") (pin "J1") (pinfunction "P0.04/AIN2_J1") (pintype "bidirectional"))
    )
    (net (code "27") (name "LED_NRF_GREEN") (class "Default")
      (node (ref "R5") (pin "2") (pinfunction "2_2") (pintype "passive"))
      (node (ref "U7") (pin "L1") (pinfunction "P0.06_L1") (pintype "bidirectional"))
    )
    (net (code "28") (name "LED_NRF_RED") (class "Default")
      (node (ref "R4") (pin "2") (pinfunction "2_2") (pintype "passive"))
      (node (ref "U7") (pin "K2") (pinfunction "P0.05/AIN3_K2") (pintype "bidirectional"))
    )
    (net (code "29") (name "LED_RED") (class "Default")
      (node (ref "R8") (pin "2") (pinfunction "2_2") (pintype "passive"))
      (node (ref "U10") (pin "39") (pinfunction "PB3_39") (pintype "bidirectional"))
    )
    (net (code "30") (name "NRF_GPIO_0") (class "Default")
      (node (ref "TP13") (pin "P$1") (pinfunction "TESTPOINT_P$1") (pintype "bidirectional"))
      (node (ref "U7") (pin "H2") (pinfunction "P0.27_H2") (pintype "bidirectional"))
    )
    (net (code "31") (name "NRF_GPIO_1") (class "Default")
      (node (ref "TP14") (pin "P$1") (pinfunction "TESTPOINT_P$1") (pintype "bidirectional"))
      (node (ref "U7") (pin "G1") (pinfunction "P0.26_G1") (pintype "bidirectional"))
    )
    (net (code "32") (name "NRF_IMU_INT1") (class "Default")
      (node (ref "U3") (pin "12") (pinfunction "INT1_12") (pintype "bidirectional"))
      (node (ref "U7") (pin "AD18") (pinfunction "P0.22_AD18") (pintype "bidirectional"))
    )
    (net (code "33") (name "NRF_IMU_INT2") (class "Default")
      (node (ref "U3") (pin "11") (pinfunction "INT2_11") (pintype "bidirectional"))
      (node (ref "U7") (pin "AD20") (pinfunction "P0.24_AD20") (pintype "bidirectional"))
    )
    (net (code "34") (name "NRF_MISO") (class "Default")
      (node (ref "J2") (pin "7") (pinfunction "DATA0/MISO_7") (pintype "bidirectional"))
      (node (ref "R15") (pin "1") (pinfunction "1_1") (pintype "passive"))
      (node (ref "U11") (pin "6") (pinfunction "SDO_6") (pintype "bidirectional"))
      (node (ref "U3") (pin "3") (pinfunction "MISO/SA0_3") (pintype "bidirectional"))
      (node (ref "U7") (pin "AD10") (pinfunction "P0.15_AD10") (pintype "bidirectional"))
    )
    (net (code "35") (name "NRF_MOSI") (class "Default")
      (node (ref "J2") (pin "3") (pinfunction "CMD/MOSI_3") (pintype "bidirectional"))
      (node (ref "R13") (pin "1") (pinfunction "1_1") (pintype "passive"))
      (node (ref "U11") (pin "9") (pinfunction "SDI_9") (pintype "bidirectional"))
      (node (ref "U3") (pin "4") (pinfunction "MOSI/SDA_4") (pintype "bidirectional"))
      (node (ref "U7") (pin "AD8") (pinfunction "P0.13_AD8") (pintype "bidirectional"))
    )
    (net (code "36") (name "NRF_SCK") (class "Default")
      (node (ref "J2") (pin "5") (pinfunction "CLK_5") (pintype "bidirectional"))
      (node (ref "U11") (pin "7") (pinfunction "SCL_7") (pintype "bidirectional"))
      (node (ref "U3") (pin "1") (pinfunction "SCL/SPC_1") (pintype "bidirectional"))
      (node (ref "U7") (pin "AD12") (pinfunction "P0.17_AD12") (pintype "bidirectional"))
    )
    (net (code "37") (name "NRF_SWDCLK") (class "Default")
      (node (ref "J4") (pin "4") (pinfunction "SWDCLK_4") (pintype "bidirectional"))
      (node (ref "U7") (pin "AA24") (pinfunction "SWDCLK_AA24") (pintype "bidirectional"))
    )
    (net (code "38") (name "NRF_SWDIO") (class "Default")
      (node (ref "J4") (pin "2") (pinfunction "SWDIO_2") (pintype "bidirectional"))
      (node (ref "U7") (pin "AC24") (pinfunction "SWDIO_AC24") (pintype "bidirectional"))
    )
    (net (code "39") (name "Net-(A4-ANTENNA)") (class "Default")
      (node (ref "A4") (pin "S1") (pinfunction "ANTENNA_S1") (pintype "bidirectional"))
      (node (ref "C2") (pin "1") (pinfunction "1_1") (pintype "bidirectional"))
      (node (ref "L1") (pin "1") (pinfunction "1_1") (pintype "bidirectional"))
    )
    (net (code "40") (name "Net-(B1-Pad+)") (class "Default")
      (node (ref "B1") (pin "+") (pinfunction "+_+") (pintype "bidirectional"))
      (node (ref "R11") (pin "2") (pinfunction "2_2") (pintype "passive"))
    )
    (net (code "41") (name "Net-(C6-2)") (class "Default")
      (node (ref "C6") (pin "P$2") (pinfunction "2_P$2") (pintype "bidirectional"))
      (node (ref "T1") (pin "3") (pinfunction "BAL/3_3") (pintype "bidirectional"))
    )
    (net (code "42") (name "Net-(C7-2)") (class "Default")
      (node (ref "C7") (pin "P$2") (pinfunction "2_P$2") (pintype "bidirectional"))
      (node (ref "T1") (pin "4") (pinfunction "BAL/4_4") (pintype "bidirectional"))
    )
    (net (code "43") (name "Net-(C17-Pad1)") (class "Default")
      (node (ref "C17") (pin "1") (pinfunction "1_1") (pintype "bidirectional"))
      (node (ref "R21") (pin "2") (pinfunction "2_2") (pintype "passive"))
    )
    (net (code "44") (name "Net-(C23-Pad1)") (class "Default")
      (node (ref "C23") (pin "1") (pinfunction "1_1") (pintype "bidirectional"))
      (node (ref "R3") (pin "2") (pinfunction "2_2") (pintype "passive"))
    )
    (net (code "45") (name "Net-(D1-PadA)") (class "Default")
      (node (ref "D1") (pin "A") (pinfunction "A_A") (pintype "passive"))
      (node (ref "R7") (pin "1") (pinfunction "1_1") (pintype "passive"))
    )
    (net (code "46") (name "Net-(D2-B)") (class "Default")
      (node (ref "D2") (pin "3") (pinfunction "B_3") (pintype "output"))
      (node (ref "R6") (pin "1") (pinfunction "1_1") (pintype "passive"))
    )
    (net (code "47") (name "Net-(D2-G)") (class "Default")
      (node (ref "D2") (pin "4") (pinfunction "G_4") (pintype "output"))
      (node (ref "R5") (pin "1") (pinfunction "1_1") (pintype "passive"))
    )
    (net (code "48") (name "Net-(D2-R)") (class "Default")
      (node (ref "D2") (pin "2") (pinfunction "R_2") (pintype "output"))
      (node (ref "R4") (pin "1") (pinfunction "1_1") (pintype "passive"))
    )
    (net (code "49") (name "Net-(D3-B)") (class "Default")
      (node (ref "D3") (pin "3") (pinfunction "B_3") (pintype "output"))
      (node (ref "R10") (pin "1") (pinfunction "1_1") (pintype "passive"))
      (node (ref "TP9") (pin "P$1") (pinfunction "TESTPOINT_P$1") (pintype "bidirectional"))
    )
    (net (code "50") (name "Net-(D3-G)") (class "Default")
      (node (ref "D3") (pin "4") (pinfunction "G_4") (pintype "output"))
      (node (ref "R9") (pin "1") (pinfunction "1_1") (pintype "passive"))
      (node (ref "TP7") (pin "P$1") (pinfunction "TESTPOINT_P$1") (pintype "bidirectional"))
    )
    (net (code "51") (name "Net-(D3-R)") (class "Default")
      (node (ref "D3") (pin "2") (pinfunction "R_2") (pintype "output"))
      (node (ref "R8") (pin "1") (pinfunction "1_1") (pintype "passive"))
      (node (ref "TP8") (pin "P$1") (pinfunction "TESTPOINT_P$1") (pintype "bidirectional"))
    )
    (net (code "52") (name "Net-(J2-VCC)") (class "Default")
      (node (ref "C62") (pin "1") (pinfunction "1_1") (pintype "bidirectional"))
      (node (ref "J2") (pin "4") (pinfunction "VCC_4") (pintype "bidirectional"))
      (node (ref "R13") (pin "2") (pinfunction "2_2") (pintype "passive"))
      (node (ref "R14") (pin "2") (pinfunction "2_2") (pintype "passive"))
      (node (ref "R15") (pin "2") (pinfunction "2_2") (pintype "passive"))
      (node (ref "R23") (pin "2") (pinfunction "2_2") (pintype "passive"))
      (node (ref "U8") (pin "1") (pinfunction "VLOAD_1") (pintype "bidirectional"))
      (node (ref "U8") (pin "2") (pinfunction "VLOAD_2") (pintype "bidirectional"))
    )
    (net (code "53") (name "Net-(L2-Pad2)") (class "Default")
      (node (ref "L2") (pin "2") (pinfunction "2_2") (pintype "bidirectional"))
      (node (ref "L3") (pin "1") (pinfunction "1_1") (pintype "bidirectional"))
    )
    (net (code "54") (name "Net-(T1-UNB)") (class "Default")
      (node (ref "T1") (pin "1") (pinfunction "UNB_1") (pintype "bidirectional"))
      (node (ref "U9") (pin "1") (pinfunction "RFC_1") (pintype "bidirectional"))
    )
    (net (code "55") (name "Net-(TP11-TESTPOINT)") (class "Default")
      (node (ref "TP11") (pin "P$1") (pinfunction "TESTPOINT_P$1") (pintype "bidirectional"))
      (node (ref "U1") (pin "36") (pinfunction "GPIO2_36") (pintype "bidirectional"))
    )
    (net (code "56") (name "Net-(TP12-TESTPOINT)") (class "Default")
      (node (ref "TP12") (pin "P$1") (pinfunction "TESTPOINT_P$1") (pintype "bidirectional"))
      (node (ref "U1") (pin "35") (pinfunction "GPIO3_35") (pintype "bidirectional"))
    )
    (net (code "57") (name "Net-(U1-CLKTUNE)") (class "Default")
      (node (ref "C3") (pin "1") (pinfunction "1_1") (pintype "bidirectional"))
      (node (ref "R21") (pin "1") (pinfunction "1_1") (pintype "passive"))
      (node (ref "U1") (pin "8") (pinfunction "CLKTUNE_8") (pintype "bidirectional"))
    )
    (net (code "58") (name "Net-(U1-VCOTUNE)") (class "Default")
      (node (ref "C16") (pin "1") (pinfunction "1_1") (pintype "bidirectional"))
      (node (ref "R3") (pin "1") (pinfunction "1_1") (pintype "passive"))
      (node (ref "U1") (pin "12") (pinfunction "VCOTUNE_12") (pintype "bidirectional"))
    )
    (net (code "59") (name "Net-(U1-VREF)") (class "Default")
      (node (ref "R19") (pin "2") (pinfunction "2_2") (pintype "passive"))
      (node (ref "U1") (pin "5") (pinfunction "VREF_5") (pintype "bidirectional"))
    )
    (net (code "60") (name "Net-(U2-3V3OUT)") (class "Default")
      (node (ref "C29") (pin "1") (pinfunction "1_1") (pintype "bidirectional"))
      (node (ref "U2") (pin "1") (pinfunction "VCCIO_1") (pintype "power_in"))
      (node (ref "U2") (pin "16") (pinfunction "3V3OUT_16") (pintype "output"))
    )
    (net (code "61") (name "Net-(U2-RXD)") (class "Default")
      (node (ref "R2") (pin "1") (pinfunction "1_1") (pintype "passive"))
      (node (ref "U2") (pin "2") (pinfunction "RXD_2") (pintype "input"))
    )
    (net (code "62") (name "Net-(U2-TXD)") (class "Default")
      (node (ref "R1") (pin "1") (pinfunction "1_1") (pintype "passive"))
      (node (ref "U2") (pin "30") (pinfunction "TXD_30") (pintype "output"))
    )
    (net (code "63") (name "Net-(U4-L1)") (class "Default")
      (node (ref "U4") (pin "1") (pinfunction "LX_1") (pintype "bidirectional"))
      (node (ref "U4") (pin "7") (pinfunction "L1_7") (pintype "bidirectional"))
    )
    (net (code "64") (name "Net-(U5-BP)") (class "Default")
      (node (ref "C24") (pin "1") (pinfunction "1_1") (pintype "bidirectional"))
      (node (ref "U5") (pin "4") (pinfunction "BP_4") (pintype "bidirectional"))
    )
    (net (code "65") (name "Net-(U6-PROG)") (class "Default")
      (node (ref "R12") (pin "2") (pinfunction "2_2") (pintype "passive"))
      (node (ref "U6") (pin "8") (pinfunction "PROG_8") (pintype "bidirectional"))
    )
    (net (code "66") (name "Net-(U6-STAT)") (class "Default")
      (node (ref "D1") (pin "C") (pinfunction "C_C") (pintype "passive"))
      (node (ref "U6") (pin "5") (pinfunction "STAT_5") (pintype "bidirectional"))
    )
    (net (code "67") (name "Net-(U7-ANT)") (class "Default")
      (node (ref "C1") (pin "1") (pinfunction "1_1") (pintype "bidirectional"))
      (node (ref "L1") (pin "2") (pinfunction "2_2") (pintype "bidirectional"))
      (node (ref "U7") (pin "H23") (pinfunction "ANT_H23") (pintype "bidirectional"))
    )
    (net (code "68") (name "Net-(U7-DCC)") (class "Default")
      (node (ref "L3") (pin "2") (pinfunction "2_2") (pintype "bidirectional"))
      (node (ref "U7") (pin "B3") (pinfunction "DCC_B3") (pintype "bidirectional"))
    )
    (net (code "69") (name "Net-(U7-DEC1)") (class "Default")
      (node (ref "C32") (pin "1") (pinfunction "1_1") (pintype "bidirectional"))
      (node (ref "U7") (pin "C1") (pinfunction "DEC1_C1") (pintype "bidirectional"))
    )
    (net (code "70") (name "Net-(U7-DEC3)") (class "Default")
      (node (ref "C19") (pin "1") (pinfunction "1_1") (pintype "bidirectional"))
      (node (ref "U7") (pin "D23") (pinfunction "DEC3_D23") (pintype "bidirectional"))
    )
    (net (code "71") (name "Net-(U7-DEC4)") (class "Default")
      (node (ref "C27") (pin "1") (pinfunction "1_1") (pintype "bidirectional"))
      (node (ref "C57") (pin "1") (pinfunction "1_1") (pintype "bidirectional"))
      (node (ref "L2") (pin "1") (pinfunction "1_1") (pintype "bidirectional"))
      (node (ref "U7") (pin "B5") (pinfunction "DEC4_B5") (pintype "bidirectional"))
      (node (ref "U7") (pin "E24") (pinfunction "DEC6_E24") (pintype "bidirectional"))
    )
    (net (code "72") (name "Net-(U7-DEC5)") (class "Default")
      (node (ref "C22") (pin "1") (pinfunction "1_1") (pintype "bidirectional"))
      (node (ref "U7") (pin "N24") (pinfunction "DEC5_N24") (pintype "bidirectional"))
    )
    (net (code "73") (name "Net-(U7-XC1)") (class "Default")
      (node (ref "C8") (pin "2") (pinfunction "2_2") (pintype "bidirectional"))
      (node (ref "U7") (pin "B24") (pinfunction "XC1_B24") (pintype "bidirectional"))
      (node (ref "X3") (pin "3") (pinfunction "2_3") (pintype "bidirectional"))
    )
    (net (code "74") (name "Net-(U7-XC2)") (class "Default")
      (node (ref "C9") (pin "2") (pinfunction "2_2") (pintype "bidirectional"))
      (node (ref "U7") (pin "A23") (pinfunction "XC2_A23") (pintype "bidirectional"))
      (node (ref "X3") (pin "1") (pinfunction "1_1") (pintype "bidirectional"))
    )
    (net (code "75") (name "Net-(U10-PF11-BOOT0)") (class "Default")
      (node (ref "R20") (pin "1") (pinfunction "1_1") (pintype "passive"))
      (node (ref "U10") (pin "44") (pinfunction "PF11-BOOT0_44") (pintype "bidirectional"))
    )
    (net (code "76") (name "Net-(U11-AF)") (class "Default")
      (node (ref "C18") (pin "1") (pinfunction "1_1") (pintype "bidirectional"))
      (node (ref "U11") (pin "14") (pinfunction "AF_14") (pintype "bidirectional"))
    )
    (net (code "77") (name "Net-(U11-EXTI)") (class "Default")
      (node (ref "R16") (pin "1") (pinfunction "1_1") (pintype "passive"))
      (node (ref "U11") (pin "10") (pinfunction "EXTI_10") (pintype "bidirectional"))
    )
    (net (code "78") (name "Net-(U11-XI)") (class "Default")
      (node (ref "U11") (pin "16") (pinfunction "XI_16") (pintype "bidirectional"))
      (node (ref "X5") (pin "1") (pinfunction "1_1") (pintype "bidirectional"))
    )
    (net (code "79") (name "Net-(U11-XO)") (class "Default")
      (node (ref "U11") (pin "15") (pinfunction "XO_15") (pintype "bidirectional"))
      (node (ref "X5") (pin "2") (pinfunction "2_2") (pintype "bidirectional"))
    )
    (net (code "80") (name "OSC_IN") (class "Default")
      (node (ref "C14") (pin "1") (pinfunction "1_1") (pintype "bidirectional"))
      (node (ref "U10") (pin "5") (pinfunction "PF0-OSC_IN_5") (pintype "bidirectional"))
      (node (ref "X2") (pin "1") (pinfunction "1_1") (pintype "bidirectional"))
    )
    (net (code "81") (name "OSC_OUT") (class "Default")
      (node (ref "C15") (pin "1") (pinfunction "1_1") (pintype "bidirectional"))
      (node (ref "U10") (pin "6") (pinfunction "PF1-OSC_OUT_6") (pintype "bidirectional"))
      (node (ref "X2") (pin "3") (pinfunction "2_3") (pintype "bidirectional"))
    )
    (net (code "82") (name "REG_EN") (class "Default")
      (node (ref "U1") (pin "21") (pinfunction "EXTON_21") (pintype "output"))
      (node (ref "U4") (pin "4") (pinfunction "CE/MODE_4") (pintype "bidirectional"))
    )
    (net (code "83") (name "RF1") (class "Default")
      (node (ref "A1") (pin "A") (pinfunction "ANTENNA_A") (pintype "bidirectional"))
      (node (ref "U9") (pin "4") (pinfunction "RF1_4") (pintype "bidirectional"))
    )
    (net (code "84") (name "RF2") (class "Default")
      (node (ref "A2") (pin "A") (pinfunction "ANTENNA_A") (pintype "bidirectional"))
      (node (ref "U9") (pin "5") (pinfunction "RF2_5") (pintype "bidirectional"))
    )
    (net (code "85") (name "RF3") (class "Default")
      (node (ref "A3") (pin "A") (pinfunction "ANTENNA_A") (pintype "bidirectional"))
      (node (ref "U9") (pin "8") (pinfunction "RF3_8") (pintype "bidirectional"))
    )
    (net (code "86") (name "RF_N") (class "Default")
      (node (ref "C6") (pin "P$1") (pinfunction "1_P$1") (pintype "bidirectional"))
      (node (ref "U1") (pin "17") (pinfunction "RF_N_17") (pintype "bidirectional"))
    )
    (net (code "87") (name "RF_P") (class "Default")
      (node (ref "C7") (pin "P$1") (pinfunction "1_P$1") (pintype "bidirectional"))
      (node (ref "U1") (pin "16") (pinfunction "RF_P_16") (pintype "bidirectional"))
    )
    (net (code "88") (name "RTC_WDI") (class "Default")
      (node (ref "R17") (pin "1") (pinfunction "1_1") (pintype "passive"))
      (node (ref "U11") (pin "2") (pinfunction "WDI_2") (pintype "bidirectional"))
      (node (ref "U7") (pin "A8") (pinfunction "P0.31/AIN7_A8") (pintype "bidirectional"))
    )
    (net (code "89") (name "SD_EN") (class "Default")
      (node (ref "R22") (pin "1") (pinfunction "1_1") (pintype "passive"))
      (node (ref "U7") (pin "AC9") (pinfunction "P0.14_AC9") (pintype "bidirectional"))
      (node (ref "U8") (pin "3") (pinfunction "EN_3") (pintype "bidirectional"))
    )
    (net (code "90") (name "STM_INTERRUPT") (class "Default")
      (node (ref "TP3") (pin "TP") (pinfunction "TP_TP") (pintype "input"))
      (node (ref "U10") (pin "12") (pinfunction "PA2_12") (pintype "bidirectional"))
      (node (ref "U7") (pin "N1") (pinfunction "P0.08_N1") (pintype "bidirectional"))
    )
    (net (code "91") (name "STM_SWCLK") (class "Default")
      (node (ref "J5") (pin "4") (pinfunction "SWDCLK_4") (pintype "bidirectional"))
      (node (ref "U10") (pin "37") (pinfunction "PA14_37") (pintype "bidirectional"))
    )
    (net (code "92") (name "STM_SWDIO") (class "Default")
      (node (ref "J5") (pin "2") (pinfunction "SWDIO_2") (pintype "bidirectional"))
      (node (ref "U10") (pin "34") (pinfunction "PA13_34") (pintype "bidirectional"))
    )
    (net (code "93") (name "VBAT") (class "Default")
      (node (ref "C60") (pin "1") (pinfunction "1_1") (pintype "bidirectional"))
      (node (ref "C69") (pin "1") (pinfunction "1_1") (pintype "bidirectional"))
      (node (ref "J3") (pin "P") (pinfunction "+_P") (pintype "bidirectional"))
      (node (ref "R26") (pin "2") (pinfunction "2_2") (pintype "passive"))
      (node (ref "U5") (pin "1") (pinfunction "IN_1") (pintype "bidirectional"))
      (node (ref "U5") (pin "3") (pinfunction "~{SHDN}_3") (pintype "bidirectional"))
      (node (ref "U6") (pin "3") (pinfunction "VBAT/3_3") (pintype "power_in"))
      (node (ref "U6") (pin "4") (pinfunction "VBAT/4_4") (pintype "power_in"))
    )
    (net (code "94") (name "VBAT_RTC") (class "Default")
      (node (ref "R11") (pin "1") (pinfunction "1_1") (pintype "passive"))
      (node (ref "R16") (pin "2") (pinfunction "2_2") (pintype "passive"))
      (node (ref "R17") (pin "2") (pinfunction "2_2") (pintype "passive"))
      (node (ref "R18") (pin "2") (pinfunction "2_2") (pintype "passive"))
      (node (ref "U11") (pin "5") (pinfunction "VBAT_5") (pintype "bidirectional"))
    )
    (net (code "95") (name "VCC") (class "Default")
      (node (ref "C59") (pin "1") (pinfunction "1_1") (pintype "bidirectional"))
      (node (ref "U11") (pin "13") (pinfunction "VCC_13") (pintype "bidirectional"))
    )
    (net (code "96") (name "VDDCLK") (class "Default")
      (node (ref "C17") (pin "2") (pinfunction "2_2") (pintype "bidirectional"))
      (node (ref "C3") (pin "2") (pinfunction "2_2") (pintype "bidirectional"))
      (node (ref "C40") (pin "1") (pinfunction "1_1") (pintype "bidirectional"))
      (node (ref "U1") (pin "9") (pinfunction "VDDCLK_9") (pintype "power_in"))
    )
    (net (code "97") (name "VDDDIG") (class "Default")
      (node (ref "C36") (pin "1") (pinfunction "1_1") (pintype "bidirectional"))
      (node (ref "C37") (pin "1") (pinfunction "1_1") (pintype "bidirectional"))
      (node (ref "U1") (pin "20") (pinfunction "VDDREG_20") (pintype "power_in"))
      (node (ref "U1") (pin "44") (pinfunction "VDDDIG_44") (pintype "power_in"))
    )
    (net (code "98") (name "VDDIF") (class "Default")
      (node (ref "C43") (pin "1") (pinfunction "1_1") (pintype "bidirectional"))
      (node (ref "U1") (pin "7") (pinfunction "VDDIF_7") (pintype "power_in"))
    )
    (net (code "99") (name "VDDIO") (class "Default")
      (node (ref "C42") (pin "1") (pinfunction "1_1") (pintype "bidirectional"))
      (node (ref "C54") (pin "1") (pinfunction "1_1") (pintype "bidirectional"))
      (node (ref "U1") (pin "31") (pinfunction "VDDIO/31_31") (pintype "power_in"))
      (node (ref "U1") (pin "42") (pinfunction "VDDIO/42_42") (pintype "power_in"))
    )
    (net (code "100") (name "VDDMS") (class "Default")
      (node (ref "C39") (pin "1") (pinfunction "1_1") (pintype "bidirectional"))
      (node (ref "U1") (pin "6") (pinfunction "VDDMS_6") (pintype "power_in"))
    )
    (net (code "101") (name "VDDSYN") (class "Default")
      (node (ref "C41") (pin "1") (pinfunction "1_1") (pintype "bidirectional"))
      (node (ref "U1") (pin "10") (pinfunction "VDDSYN_10") (pintype "power_in"))
    )
    (net (code "102") (name "VDDVCO") (class "Default")
      (node (ref "C16") (pin "2") (pinfunction "2_2") (pintype "bidirectional"))
      (node (ref "C23") (pin "2") (pinfunction "2_2") (pintype "bidirectional"))
      (node (ref "C44") (pin "1") (pinfunction "1_1") (pintype "bidirectional"))
      (node (ref "U1") (pin "11") (pinfunction "VDDVCO_11") (pintype "power_in"))
    )
    (net (code "103") (name "VUSB") (class "Default")
      (node (ref "C55") (pin "1") (pinfunction "1_1") (pintype "bidirectional"))
      (node (ref "C68") (pin "1") (pinfunction "1_1") (pintype "bidirectional"))
      (node (ref "J1") (pin "1") (pinfunction "+5V_1") (pintype "bidirectional"))
      (node (ref "R7") (pin "2") (pinfunction "2_2") (pintype "passive"))
      (node (ref "U2") (pin "19") (pinfunction "VCC_19") (pintype "power_in"))
      (node (ref "U6") (pin "1") (pinfunction "VDD/1_1") (pintype "power_in"))
      (node (ref "U6") (pin "2") (pinfunction "VDD/2_2") (pintype "power_in"))
    )
    (net (code "104") (name "XL3") (class "Default")
      (node (ref "C11") (pin "2") (pinfunction "2_2") (pintype "bidirectional"))
      (node (ref "U7") (pin "D2") (pinfunction "P0.00/XL1_D2") (pintype "bidirectional"))
      (node (ref "X1") (pin "A") (pinfunction "1_A") (pintype "bidirectional"))
    )
    (net (code "105") (name "XL4") (class "Default")
      (node (ref "C10") (pin "2") (pinfunction "2_2") (pintype "bidirectional"))
      (node (ref "U7") (pin "F2") (pinfunction "P0.01/XL2_F2") (pintype "bidirectional"))
      (node (ref "X1") (pin "B") (pinfunction "2_B") (pintype "bidirectional"))
    )
    (net (code "106") (name "XTAL1") (class "Default")
      (node (ref "C13") (pin "1") (pinfunction "1_1") (pintype "bidirectional"))
      (node (ref "U1") (pin "3") (pinfunction "XTAL1_3") (pintype "input"))
      (node (ref "X4") (pin "3") (pinfunction "2_3") (pintype "bidirectional"))
    )
    (net (code "107") (name "XTAL2") (class "Default")
      (node (ref "C12") (pin "1") (pinfunction "1_1") (pintype "bidirectional"))
      (node (ref "U1") (pin "4") (pinfunction "XTAL2_4") (pintype "input"))
      (node (ref "X4") (pin "1") (pinfunction "1_1") (pintype "bidirectional"))
    )
    (net (code "108") (name "unconnected-(J1-ID-Pad4)") (class "Default")
      (node (ref "J1") (pin "4") (pinfunction "ID_4") (pintype "bidirectional"))
    )
    (net (code "109") (name "unconnected-(J2-DATA1{slash}RSV-Pad8)") (class "Default")
      (node (ref "J2") (pin "8") (pinfunction "DATA1/RSV_8") (pintype "bidirectional"))
    )
    (net (code "110") (name "unconnected-(J2-DATA2{slash}NC-Pad1)") (class "Default")
      (node (ref "J2") (pin "1") (pinfunction "DATA2/NC_1") (pintype "bidirectional"))
    )
    (net (code "111") (name "unconnected-(J4-SWO-Pad6)") (class "Default")
      (node (ref "J4") (pin "6") (pinfunction "SWO_6") (pintype "bidirectional"))
    )
    (net (code "112") (name "unconnected-(J5-SWO-Pad6)") (class "Default")
      (node (ref "J5") (pin "6") (pinfunction "SWO_6") (pintype "bidirectional"))
    )
    (net (code "113") (name "unconnected-(U1-GPIO0-Pad38)") (class "Default")
      (node (ref "U1") (pin "38") (pinfunction "GPIO0_38") (pintype "bidirectional"))
    )
    (net (code "114") (name "unconnected-(U1-GPIO1-Pad37)") (class "Default")
      (node (ref "U1") (pin "37") (pinfunction "GPIO1_37") (pintype "bidirectional"))
    )
    (net (code "115") (name "unconnected-(U1-GPIO4-Pad34)") (class "Default")
      (node (ref "U1") (pin "34") (pinfunction "GPIO4_34") (pintype "bidirectional"))
    )
    (net (code "116") (name "unconnected-(U1-GPIO5-Pad33)") (class "Default")
      (node (ref "U1") (pin "33") (pinfunction "GPIO5_33") (pintype "bidirectional"))
    )
    (net (code "117") (name "unconnected-(U1-GPIO6-Pad30)") (class "Default")
      (node (ref "U1") (pin "30") (pinfunction "GPIO6_30") (pintype "bidirectional"))
    )
    (net (code "118") (name "unconnected-(U2-CBUS0-Pad22)") (class "Default")
      (node (ref "U2") (pin "22") (pinfunction "CBUS0_22") (pintype "bidirectional"))
    )
    (net (code "119") (name "unconnected-(U2-CBUS1-Pad21)") (class "Default")
      (node (ref "U2") (pin "21") (pinfunction "CBUS1_21") (pintype "bidirectional"))
    )
    (net (code "120") (name "unconnected-(U2-CBUS2-Pad10)") (class "Default")
      (node (ref "U2") (pin "10") (pinfunction "CBUS2_10") (pintype "bidirectional"))
    )
    (net (code "121") (name "unconnected-(U2-CBUS3-Pad11)") (class "Default")
      (node (ref "U2") (pin "11") (pinfunction "CBUS3_11") (pintype "bidirectional"))
    )
    (net (code "122") (name "unconnected-(U2-CBUS4-Pad9)") (class "Default")
      (node (ref "U2") (pin "9") (pinfunction "CBUS4_9") (pintype "bidirectional"))
    )
    (net (code "123") (name "unconnected-(U2-OSCI-Pad27)") (class "Default")
      (node (ref "U2") (pin "27") (pinfunction "OSCI_27") (pintype "input"))
    )
    (net (code "124") (name "unconnected-(U2-OSCO-Pad28)") (class "Default")
      (node (ref "U2") (pin "28") (pinfunction "OSCO_28") (pintype "output"))
    )
    (net (code "125") (name "unconnected-(U2-~{CTS}-Pad8)") (class "Default")
      (node (ref "U2") (pin "8") (pinfunction "~{CTS}_8") (pintype "input"))
    )
    (net (code "126") (name "unconnected-(U2-~{DCD}-Pad7)") (class "Default")
      (node (ref "U2") (pin "7") (pinfunction "~{DCD}_7") (pintype "input"))
    )
    (net (code "127") (name "unconnected-(U2-~{DSR}-Pad6)") (class "Default")
      (node (ref "U2") (pin "6") (pinfunction "~{DSR}_6") (pintype "input"))
    )
    (net (code "128") (name "unconnected-(U2-~{DTR}-Pad31)") (class "Default")
      (node (ref "U2") (pin "31") (pinfunction "~{DTR}_31") (pintype "output"))
    )
    (net (code "129") (name "unconnected-(U2-~{RI}-Pad3)") (class "Default")
      (node (ref "U2") (pin "3") (pinfunction "~{RI}_3") (pintype "input"))
    )
    (net (code "130") (name "unconnected-(U2-~{RTS}-Pad32)") (class "Default")
      (node (ref "U2") (pin "32") (pinfunction "~{RTS}_32") (pintype "output"))
    )
    (net (code "131") (name "unconnected-(U6-NC-Pad7)") (class "Default")
      (node (ref "U6") (pin "7") (pinfunction "NC_7") (pintype "no_connect"))
    )
    (net (code "132") (name "unconnected-(U7-D+-PadAD6)") (class "Default")
      (node (ref "U7") (pin "AD6") (pinfunction "D+_AD6") (pintype "bidirectional"))
    )
    (net (code "133") (name "unconnected-(U7-D--PadAD4)") (class "Default")
      (node (ref "U7") (pin "AD4") (pinfunction "D-_AD4") (pintype "bidirectional"))
    )
    (net (code "134") (name "unconnected-(U7-DCCH-PadAB2)") (class "Default")
      (node (ref "U7") (pin "AB2") (pinfunction "DCCH_AB2") (pintype "bidirectional"))
    )
    (net (code "135") (name "unconnected-(U7-DEC2-PadA18)") (class "Default")
      (node (ref "U7") (pin "A18") (pinfunction "DEC2_A18") (pintype "bidirectional"))
    )
    (net (code "136") (name "unconnected-(U7-DECUSB-PadAC5)") (class "Default")
      (node (ref "U7") (pin "AC5") (pinfunction "DECUSB_AC5") (pintype "bidirectional"))
    )
    (net (code "137") (name "unconnected-(U7-P0.03{slash}AIN1-PadB13)") (class "Default")
      (node (ref "U7") (pin "B13") (pinfunction "P0.03/AIN1_B13") (pintype "bidirectional"))
    )
    (net (code "138") (name "unconnected-(U7-P0.09{slash}NFC1-PadL24)") (class "Default")
      (node (ref "U7") (pin "L24") (pinfunction "P0.09/NFC1_L24") (pintype "bidirectional"))
    )
    (net (code "139") (name "unconnected-(U7-P0.10{slash}NFC2-PadJ24)") (class "Default")
      (node (ref "U7") (pin "J24") (pinfunction "P0.10/NFC2_J24") (pintype "bidirectional"))
    )
    (net (code "140") (name "unconnected-(U7-P0.19-PadAC15)") (class "Default")
      (node (ref "U7") (pin "AC15") (pinfunction "P0.19_AC15") (pintype "bidirectional"))
    )
    (net (code "141") (name "unconnected-(U7-P0.21-PadAC17)") (class "Default")
      (node (ref "U7") (pin "AC17") (pinfunction "P0.21_AC17") (pintype "bidirectional"))
    )
    (net (code "142") (name "unconnected-(U7-P0.23-PadAC19)") (class "Default")
      (node (ref "U7") (pin "AC19") (pinfunction "P0.23_AC19") (pintype "bidirectional"))
    )
    (net (code "143") (name "unconnected-(U7-P0.25-PadAC21)") (class "Default")
      (node (ref "U7") (pin "AC21") (pinfunction "P0.25_AC21") (pintype "bidirectional"))
    )
    (net (code "144") (name "unconnected-(U7-P0.28{slash}AIN4-PadB11)") (class "Default")
      (node (ref "U7") (pin "B11") (pinfunction "P0.28/AIN4_B11") (pintype "bidirectional"))
    )
    (net (code "145") (name "unconnected-(U7-P1.01-PadY23)") (class "Default")
      (node (ref "U7") (pin "Y23") (pinfunction "P1.01_Y23") (pintype "bidirectional"))
    )
    (net (code "146") (name "unconnected-(U7-P1.02-PadW24)") (class "Default")
      (node (ref "U7") (pin "W24") (pinfunction "P1.02_W24") (pintype "bidirectional"))
    )
    (net (code "147") (name "unconnected-(U7-P1.03-PadV23)") (class "Default")
      (node (ref "U7") (pin "V23") (pinfunction "P1.03_V23") (pintype "bidirectional"))
    )
    (net (code "148") (name "unconnected-(U7-P1.04-PadU24)") (class "Default")
      (node (ref "U7") (pin "U24") (pinfunction "P1.04_U24") (pintype "bidirectional"))
    )
    (net (code "149") (name "unconnected-(U7-P1.05-PadT23)") (class "Default")
      (node (ref "U7") (pin "T23") (pinfunction "P1.05_T23") (pintype "bidirectional"))
    )
    (net (code "150") (name "unconnected-(U7-P1.06-PadR24)") (class "Default")
      (node (ref "U7") (pin "R24") (pinfunction "P1.06_R24") (pintype "bidirectional"))
    )
    (net (code "151") (name "unconnected-(U7-P1.07-PadP23)") (class "Default")
      (node (ref "U7") (pin "P23") (pinfunction "P1.07_P23") (pintype "bidirectional"))
    )
    (net (code "152") (name "unconnected-(U7-P1.10-PadA20)") (class "Default")
      (node (ref "U7") (pin "A20") (pinfunction "P1.10_A20") (pintype "bidirectional"))
    )
    (net (code "153") (name "unconnected-(U7-P1.11-PadB19)") (class "Default")
      (node (ref "U7") (pin "B19") (pinfunction "P1.11_B19") (pintype "bidirectional"))
    )
    (net (code "154") (name "unconnected-(U7-P1.12-PadB17)") (class "Default")
      (node (ref "U7") (pin "B17") (pinfunction "P1.12_B17") (pintype "bidirectional"))
    )
    (net (code "155") (name "unconnected-(U7-P1.13-PadA16)") (class "Default")
      (node (ref "U7") (pin "A16") (pinfunction "P1.13_A16") (pintype "bidirectional"))
    )
    (net (code "156") (name "unconnected-(U7-P1.14-PadB15)") (class "Default")
      (node (ref "U7") (pin "B15") (pinfunction "P1.14_B15") (pintype "bidirectional"))
    )
    (net (code "157") (name "unconnected-(U7-P1.15-PadA14)") (class "Default")
      (node (ref "U7") (pin "A14") (pinfunction "P1.15_A14") (pintype "bidirectional"))
    )
    (net (code "158") (name "unconnected-(U10-PA0-Pad10)") (class "Default")
      (node (ref "U10") (pin "10") (pinfunction "PA0_10") (pintype "bidirectional"))
    )
    (net (code "159") (name "unconnected-(U10-PA1-Pad11)") (class "Default")
      (node (ref "U10") (pin "11") (pinfunction "PA1_11") (pintype "bidirectional"))
    )
    (net (code "160") (name "unconnected-(U10-PA3-Pad13)") (class "Default")
      (node (ref "U10") (pin "13") (pinfunction "PA3_13") (pintype "bidirectional"))
    )
    (net (code "161") (name "unconnected-(U10-PA11-Pad32)") (class "Default")
      (node (ref "U10") (pin "32") (pinfunction "PA11_32") (pintype "bidirectional"))
    )
    (net (code "162") (name "unconnected-(U10-PA12-Pad33)") (class "Default")
      (node (ref "U10") (pin "33") (pinfunction "PA12_33") (pintype "bidirectional"))
    )
    (net (code "163") (name "unconnected-(U10-PA15-Pad38)") (class "Default")
      (node (ref "U10") (pin "38") (pinfunction "PA15_38") (pintype "bidirectional"))
    )
    (net (code "164") (name "unconnected-(U10-PB8-Pad45)") (class "Default")
      (node (ref "U10") (pin "45") (pinfunction "PB8_45") (pintype "bidirectional"))
    )
    (net (code "165") (name "unconnected-(U10-PB9-Pad46)") (class "Default")
      (node (ref "U10") (pin "46") (pinfunction "PB9_46") (pintype "bidirectional"))
    )
    (net (code "166") (name "unconnected-(U10-PB10-Pad21)") (class "Default")
      (node (ref "U10") (pin "21") (pinfunction "PB10_21") (pintype "bidirectional"))
    )
    (net (code "167") (name "unconnected-(U10-PB11-Pad22)") (class "Default")
      (node (ref "U10") (pin "22") (pinfunction "PB11_22") (pintype "bidirectional"))
    )
    (net (code "168") (name "unconnected-(U10-PC13-Pad2)") (class "Default")
      (node (ref "U10") (pin "2") (pinfunction "PC13_2") (pintype "bidirectional"))
    )
    (net (code "169") (name "unconnected-(U10-PC14-OSC32_IN-Pad3)") (class "Default")
      (node (ref "U10") (pin "3") (pinfunction "PC14-OSC32_IN_3") (pintype "bidirectional"))
    )
    (net (code "170") (name "unconnected-(U10-PC15-OSC32_OUT-Pad4)") (class "Default")
      (node (ref "U10") (pin "4") (pinfunction "PC15-OSC32_OUT_4") (pintype "bidirectional"))
    )
    (net (code "171") (name "unconnected-(U11-CLKOUT{slash}~{IRQ3}-Pad8)") (class "Default")
      (node (ref "U11") (pin "8") (pinfunction "CLKOUT/~{IRQ3}_8") (pintype "bidirectional"))
    )
    (net (code "172") (name "unconnected-(U11-~{IRQ2}-Pad4)") (class "Default")
      (node (ref "U11") (pin "4") (pinfunction "~{IRQ2}_4") (pintype "bidirectional"))
    )
    (net (code "173") (name "unconnected-(U11-~{RST}-Pad1)") (class "Default")
      (node (ref "U11") (pin "1") (pinfunction "~{RST}_1") (pintype "bidirectional"))
    )
    (net (code "174") (name "~{DW_RST}") (class "Default")
      (node (ref "U1") (pin "27") (pinfunction "~{RST}_27") (pintype "bidirectional"))
      (node (ref "U10") (pin "18") (pinfunction "PB0_18") (pintype "bidirectional"))
    )
    (net (code "175") (name "~{DW_SPI_CS}") (class "Default")
      (node (ref "U1") (pin "24") (pinfunction "~{SPICS}_24") (pintype "input"))
      (node (ref "U10") (pin "14") (pinfunction "PA4_14") (pintype "bidirectional"))
    )
    (net (code "176") (name "~{FT_RST}") (class "Default")
      (node (ref "U2") (pin "18") (pinfunction "~{RESET}_18") (pintype "input"))
      (node (ref "U7") (pin "P2") (pinfunction "P1.08_P2") (pintype "bidirectional"))
    )
    (net (code "177") (name "~{NRF_CS_IMU}") (class "Default")
      (node (ref "U3") (pin "2") (pinfunction "CS_2") (pintype "bidirectional"))
      (node (ref "U7") (pin "AC11") (pinfunction "P0.16_AC11") (pintype "bidirectional"))
    )
    (net (code "178") (name "~{NRF_CS_RTC}") (class "Default")
      (node (ref "R18") (pin "1") (pinfunction "1_1") (pintype "passive"))
      (node (ref "U11") (pin "12") (pinfunction "~{CS}_12") (pintype "bidirectional"))
      (node (ref "U7") (pin "A10") (pinfunction "P0.29/AIN5_A10") (pintype "bidirectional"))
    )
    (net (code "179") (name "~{NRF_CS_SD}") (class "Default")
      (node (ref "J2") (pin "2") (pinfunction "DATA3-CD/CS_N_2") (pintype "bidirectional"))
      (node (ref "R14") (pin "1") (pinfunction "1_1") (pintype "passive"))
      (node (ref "U7") (pin "AD16") (pinfunction "P0.20_AD16") (pintype "bidirectional"))
    )
    (net (code "180") (name "~{NRF_RST}") (class "Default")
      (node (ref "J4") (pin "3") (pinfunction "~{RESET}_3") (pintype "bidirectional"))
      (node (ref "U7") (pin "AC13") (pinfunction "P0.18_AC13") (pintype "bidirectional"))
    )
    (net (code "181") (name "~{RTC_IRQ}") (class "Default")
      (node (ref "U11") (pin "11") (pinfunction "FOUT/~{IRQ1}_11") (pintype "bidirectional"))
      (node (ref "U7") (pin "A12") (pinfunction "P0.02/AIN0_A12") (pintype "bidirectional"))
    )
    (net (code "182") (name "~{SD_DETECT}") (class "Default")
      (node (ref "J2") (pin "A") (pinfunction "A_A") (pintype "bidirectional"))
      (node (ref "R23") (pin "1") (pinfunction "1_1") (pintype "passive"))
      (node (ref "U7") (pin "AD22") (pinfunction "P1.00_AD22") (pintype "bidirectional"))
    )
    (net (code "183") (name "~{STM_RST}") (class "Default")
      (node (ref "J5") (pin "3") (pinfunction "~{RESET}_3") (pintype "bidirectional"))
      (node (ref "U10") (pin "7") (pinfunction "~{RST}_7") (pintype "bidirectional"))
    )
  )
)
